# seedrum_shield_v1.net
KiCad netlist of a schematic drawn in EasyEDA
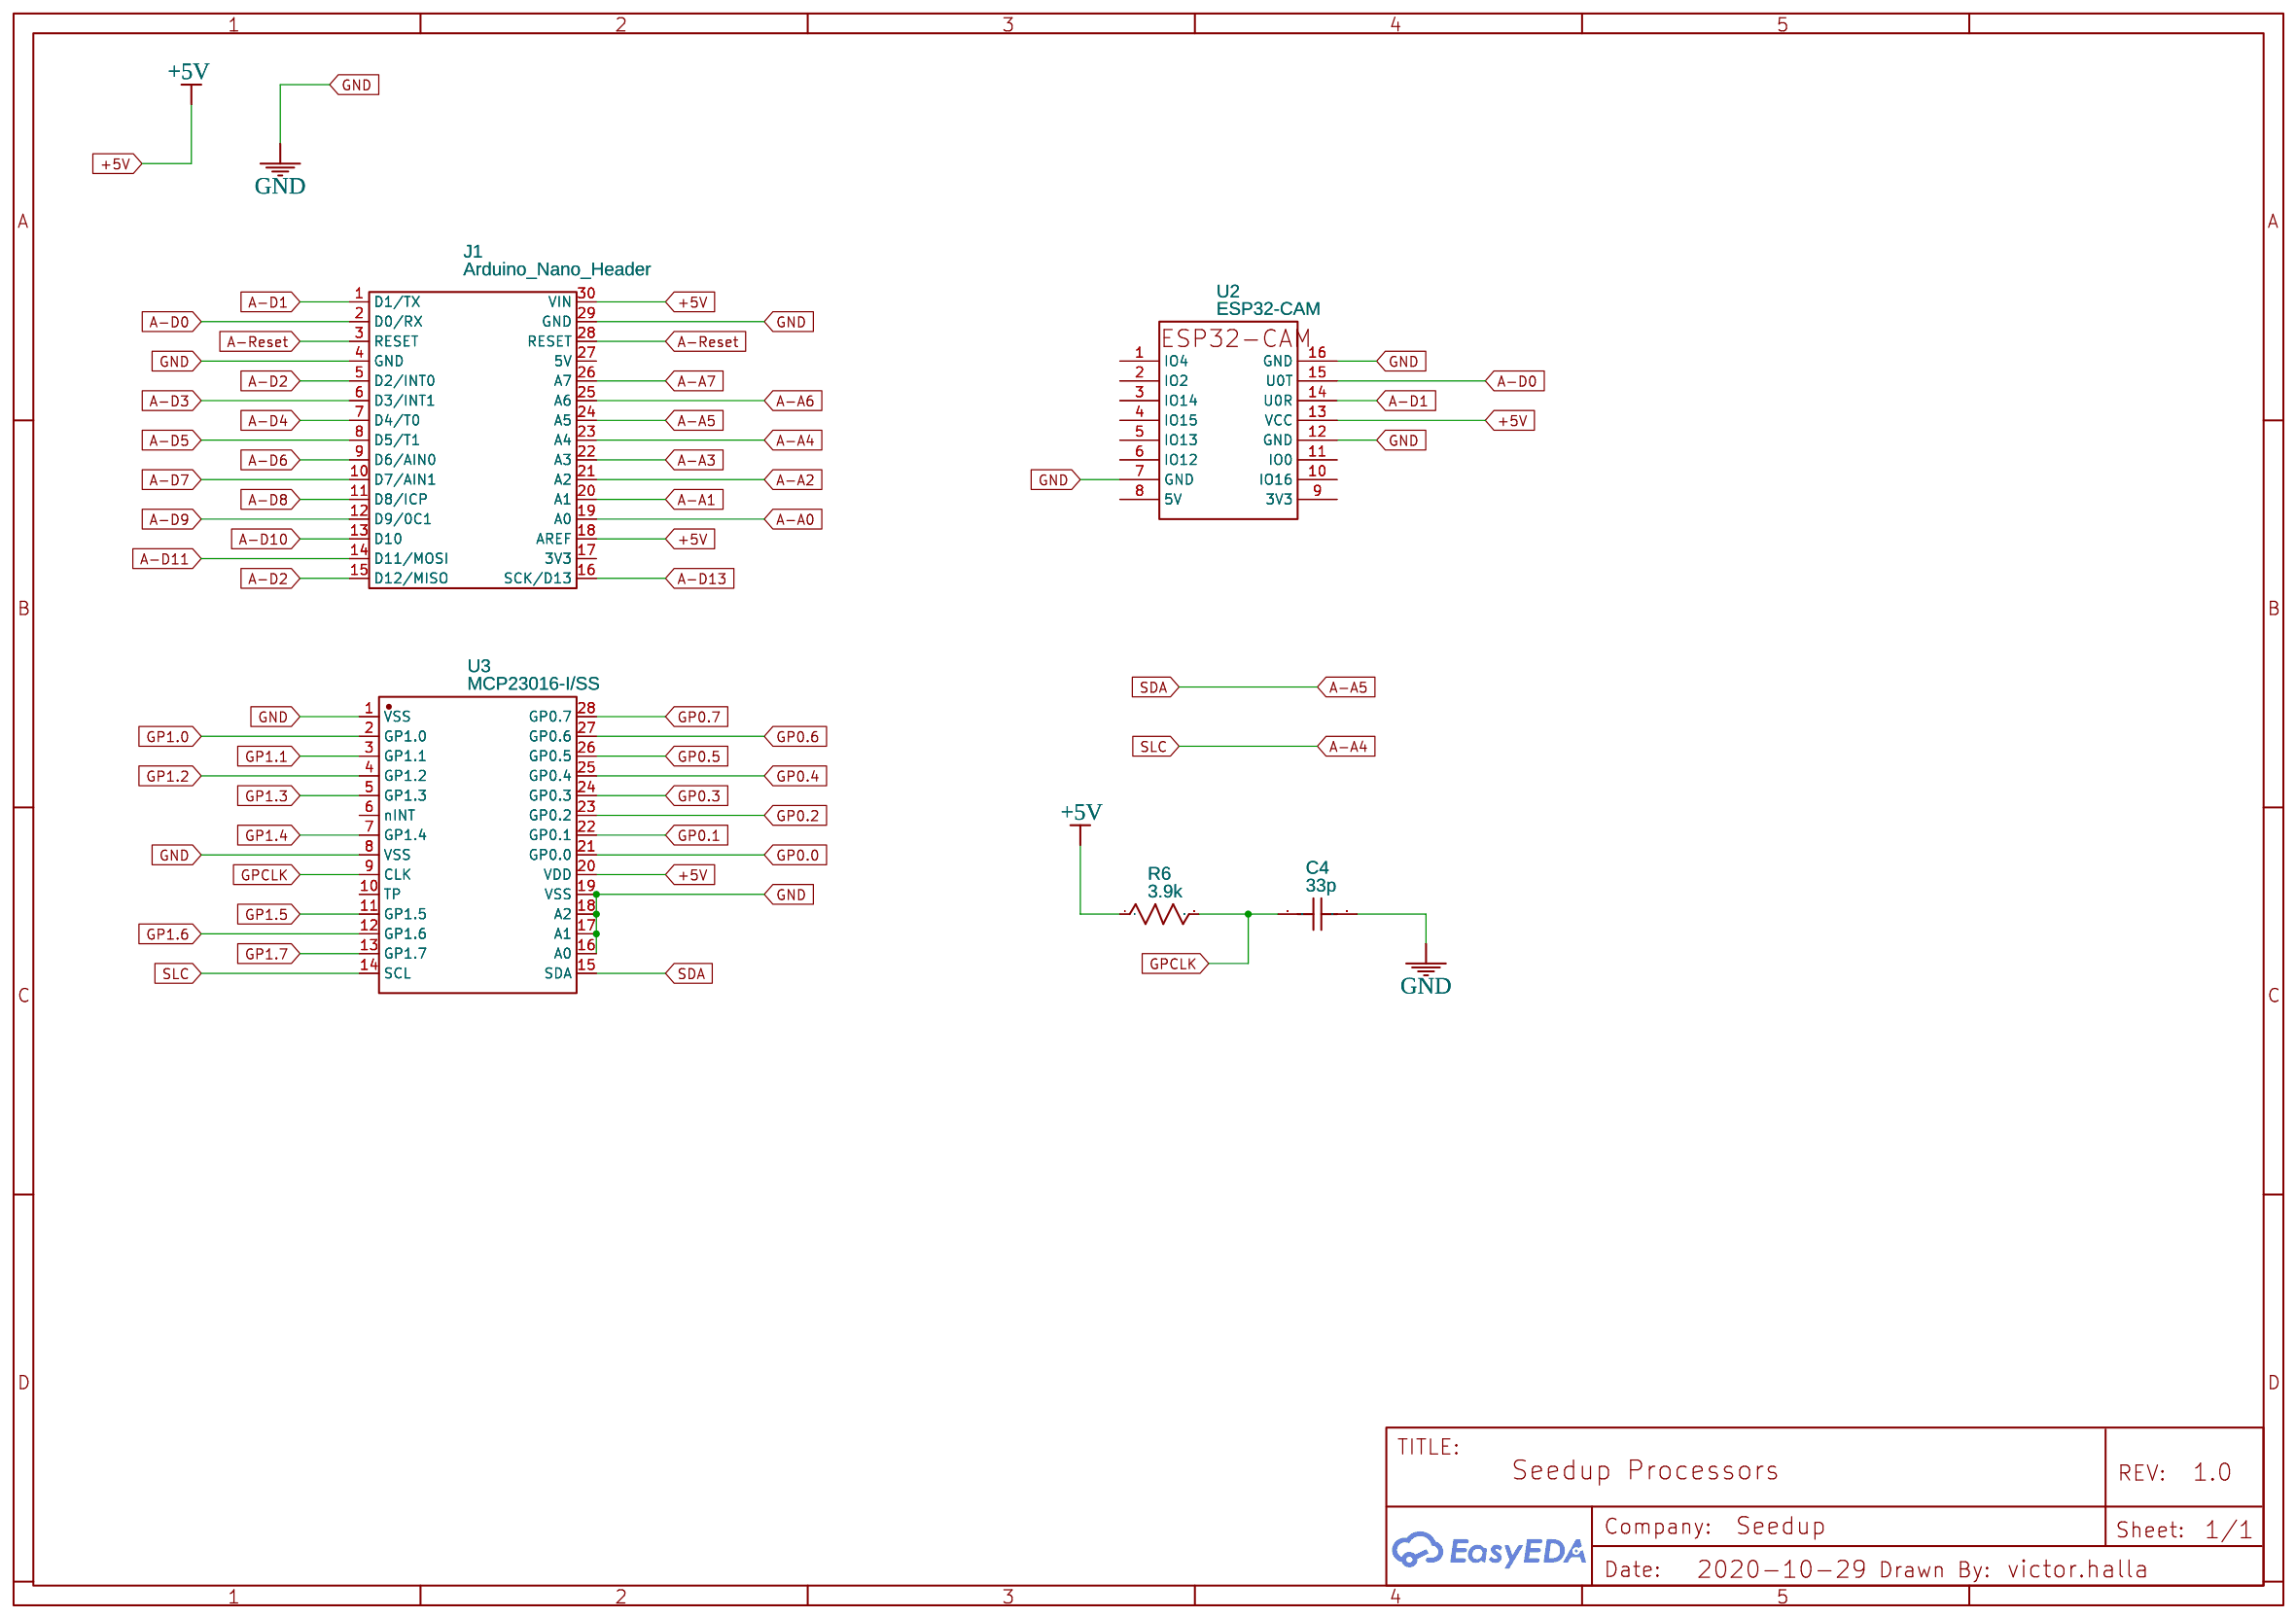
[diagram p0: Main Shield]
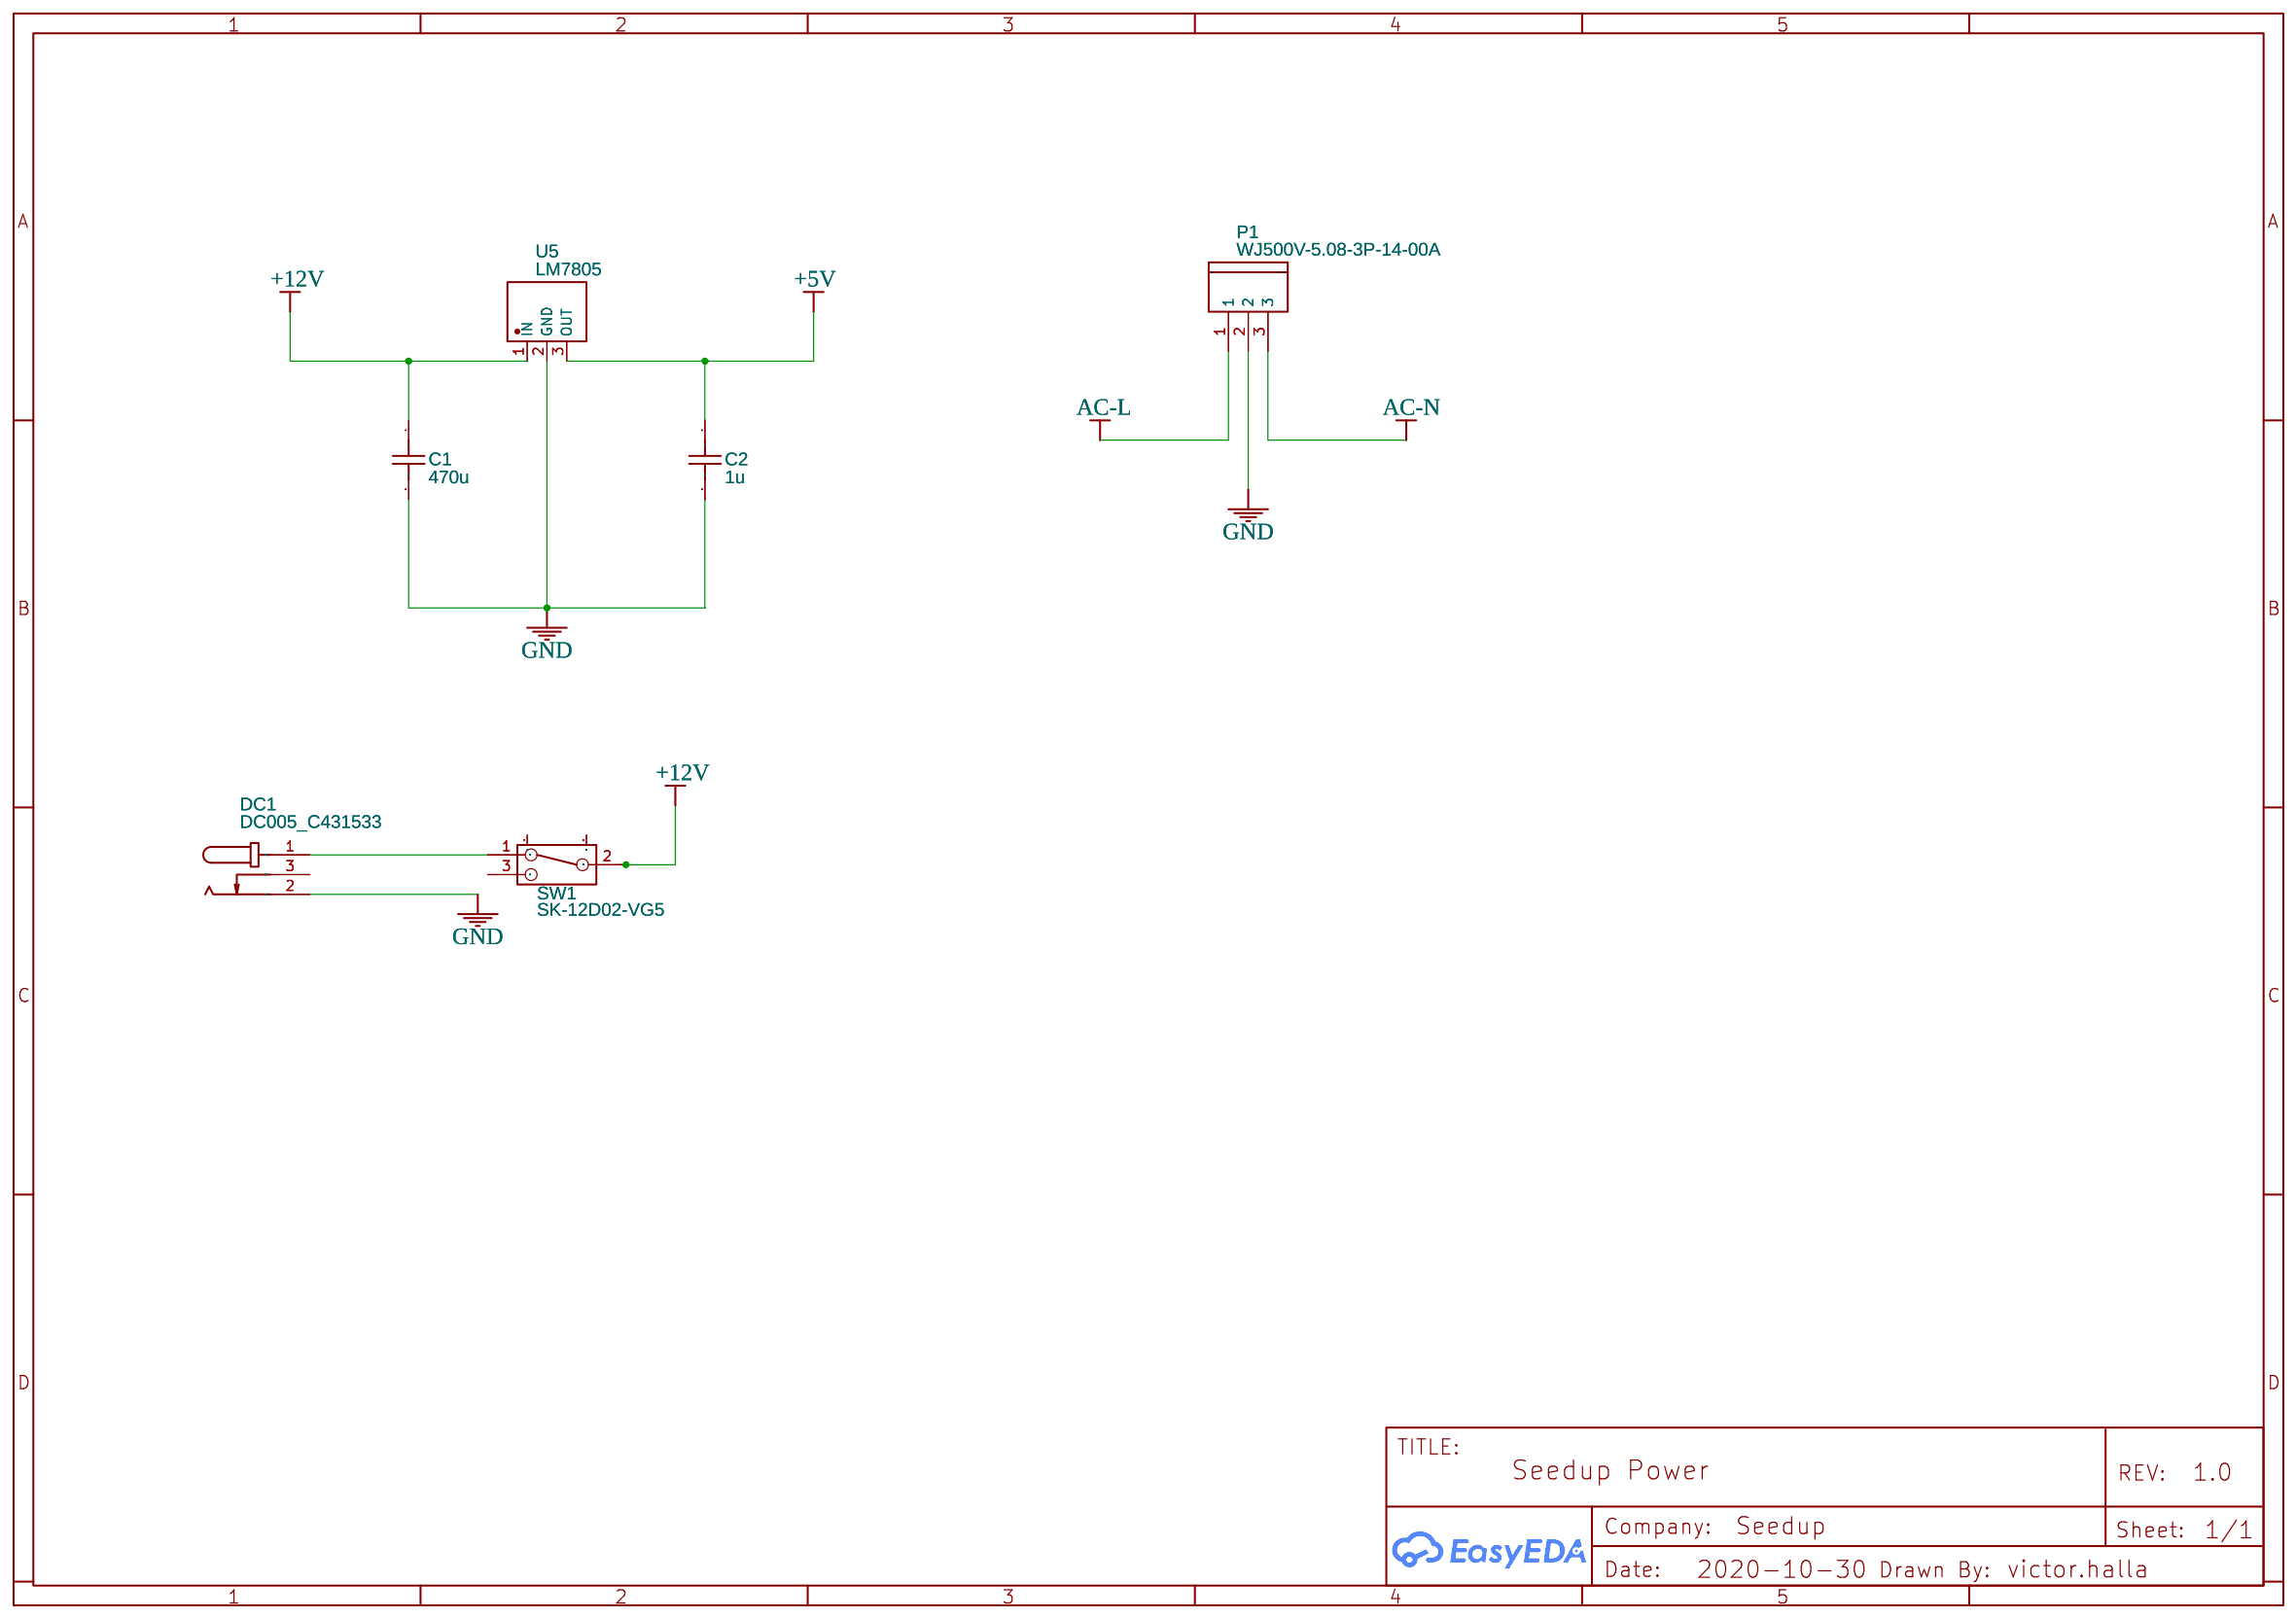
[diagram p1: Power]
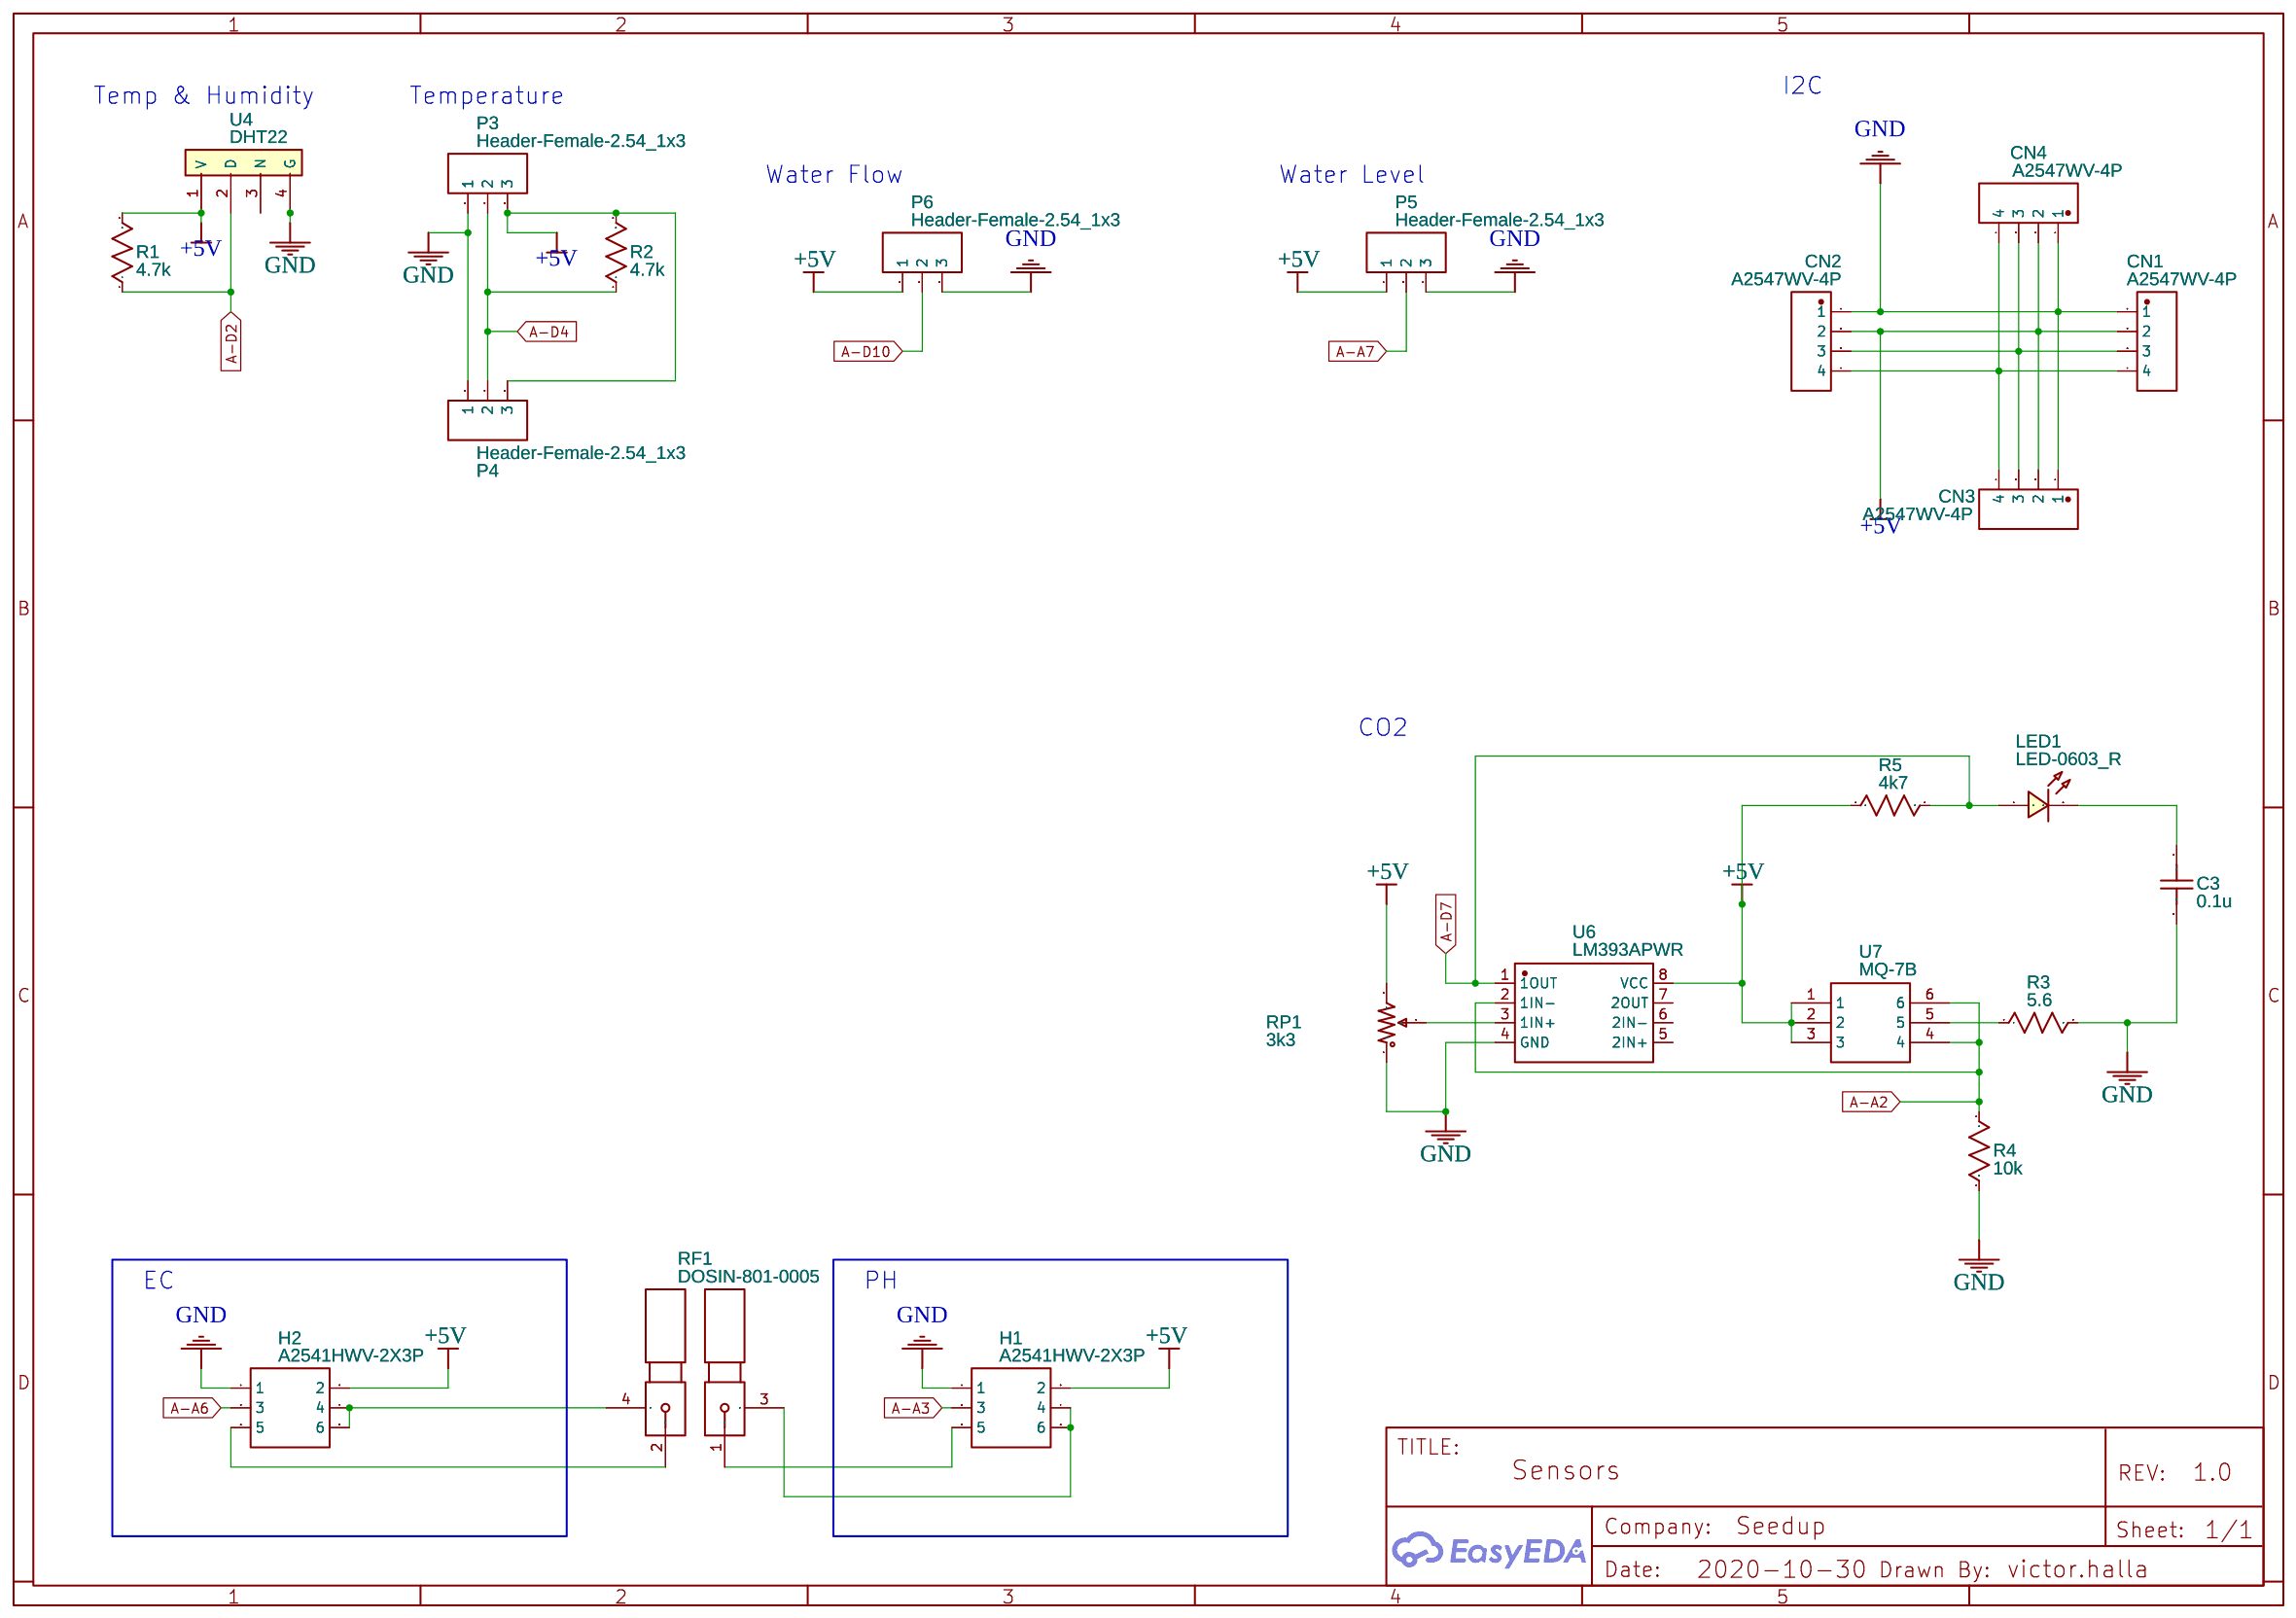
[diagram p2: Sensors]
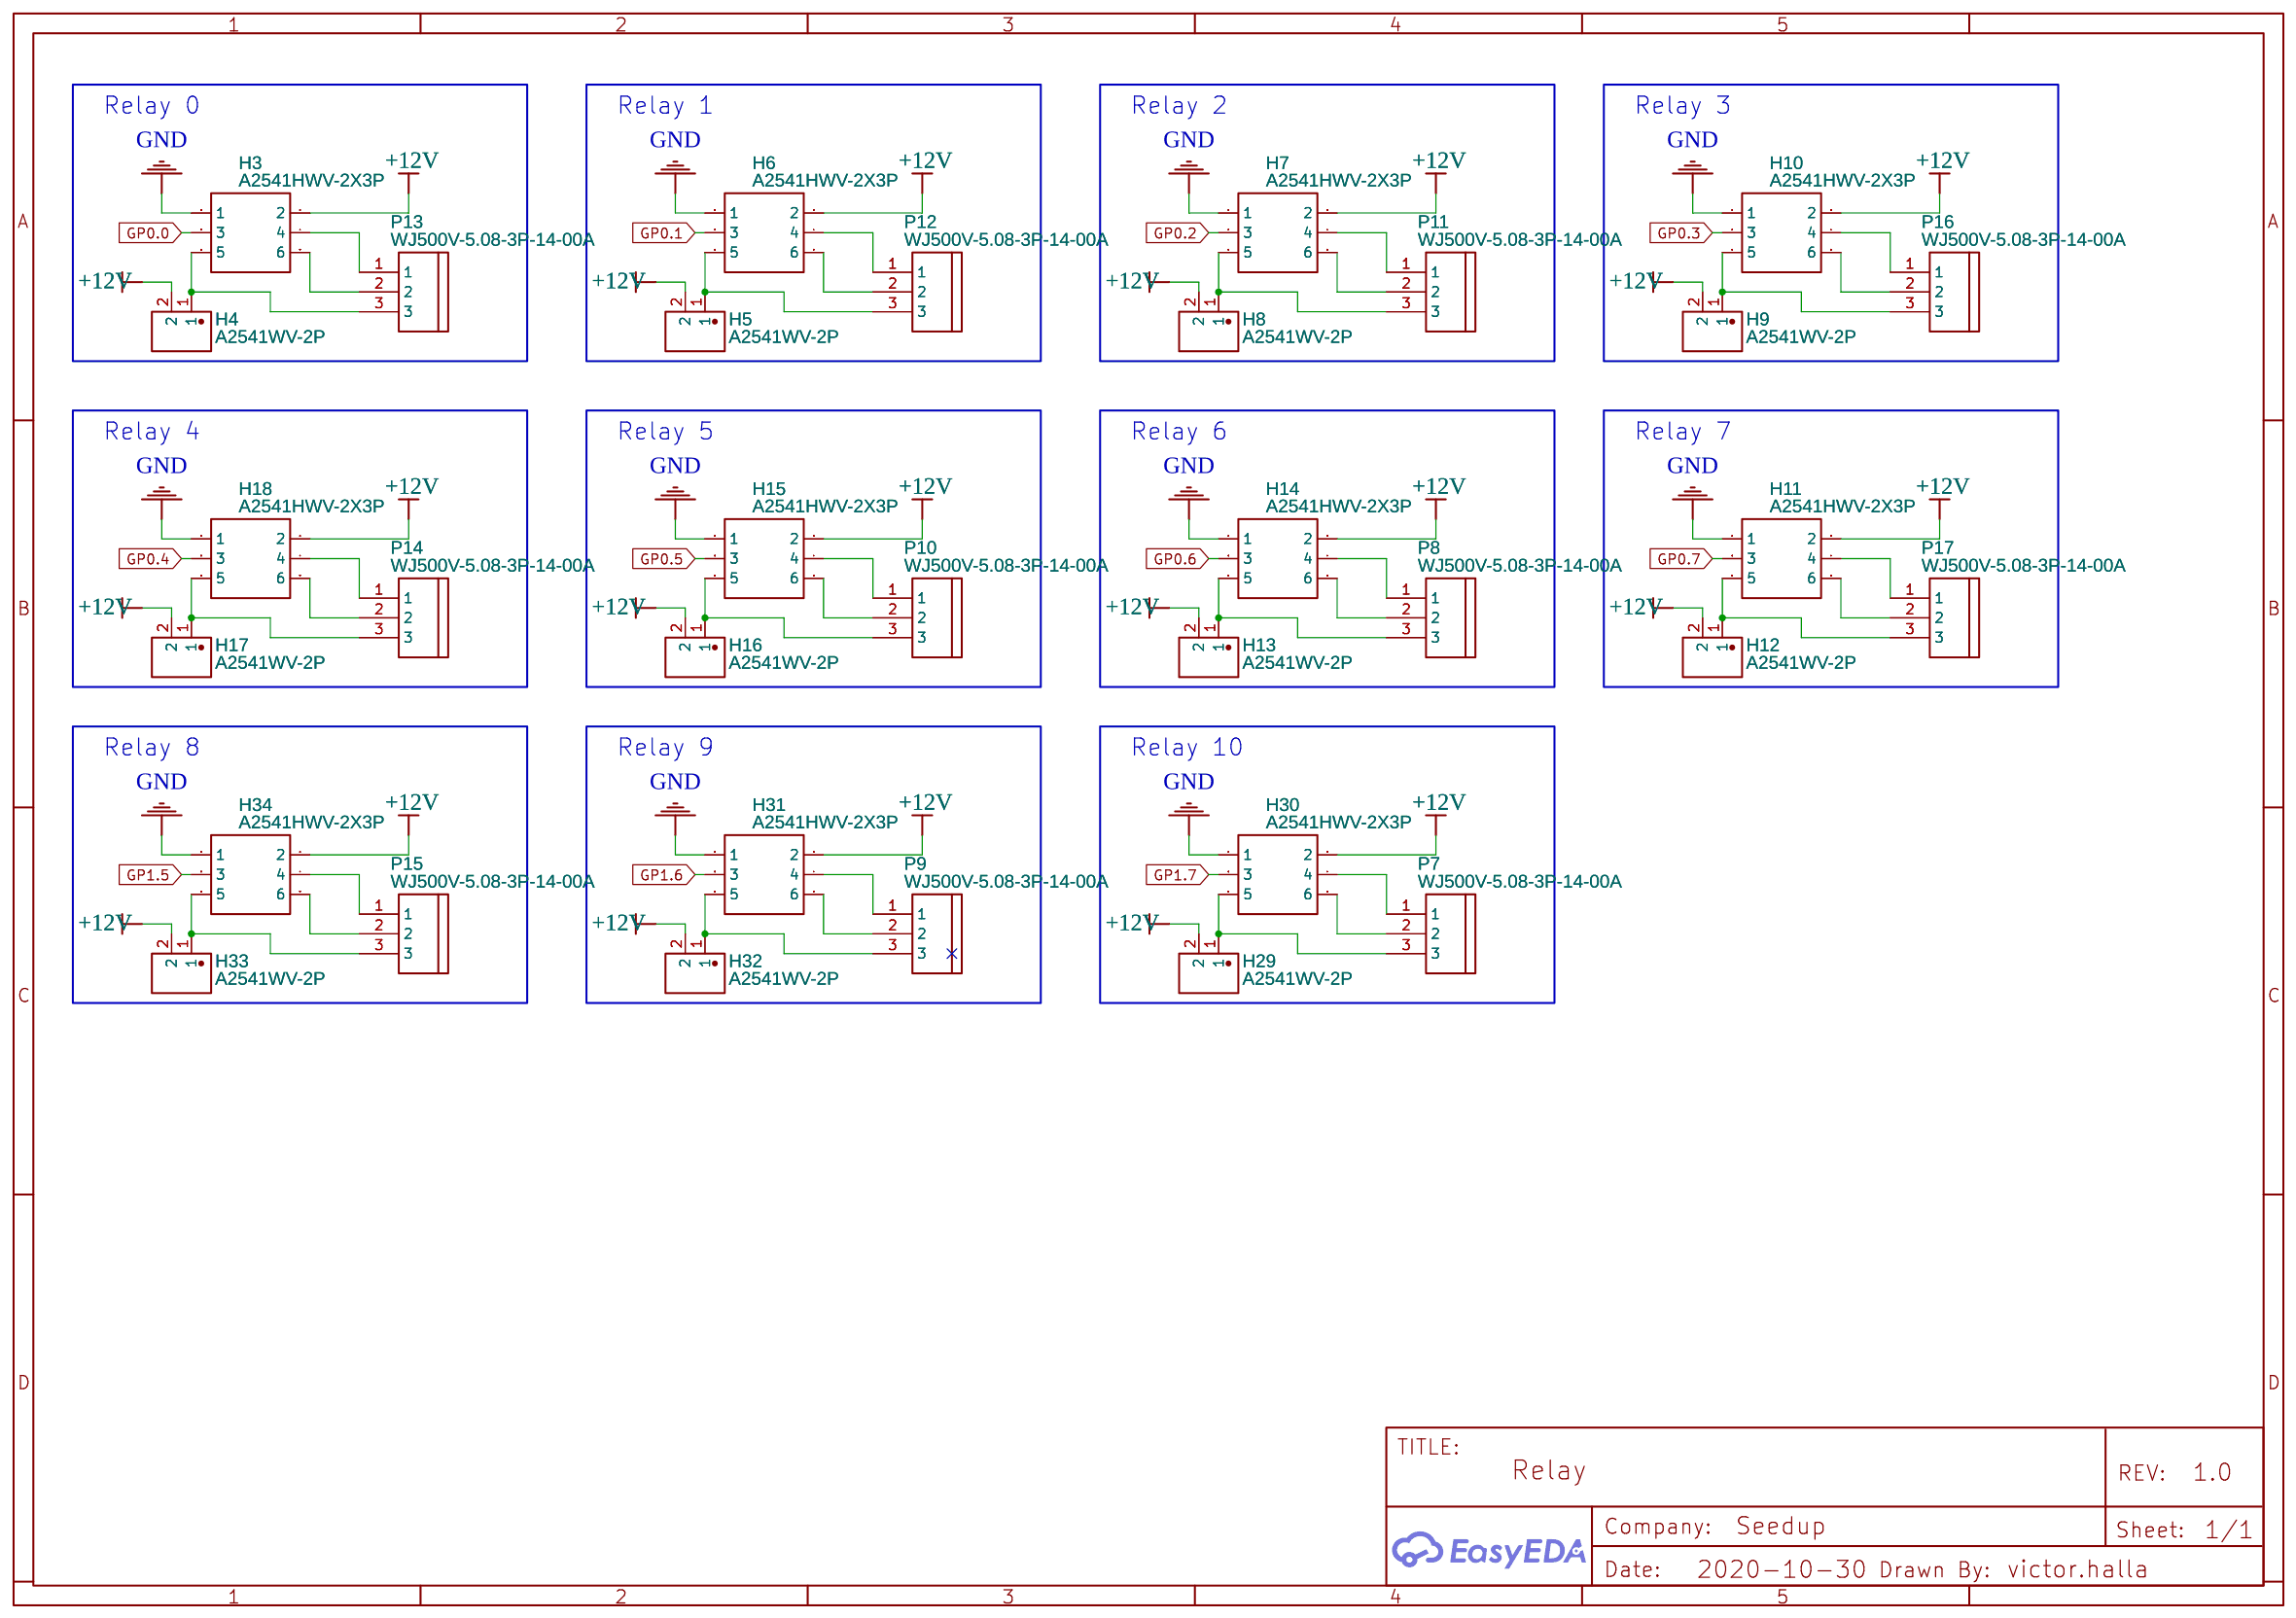
[diagram p3: Relay]
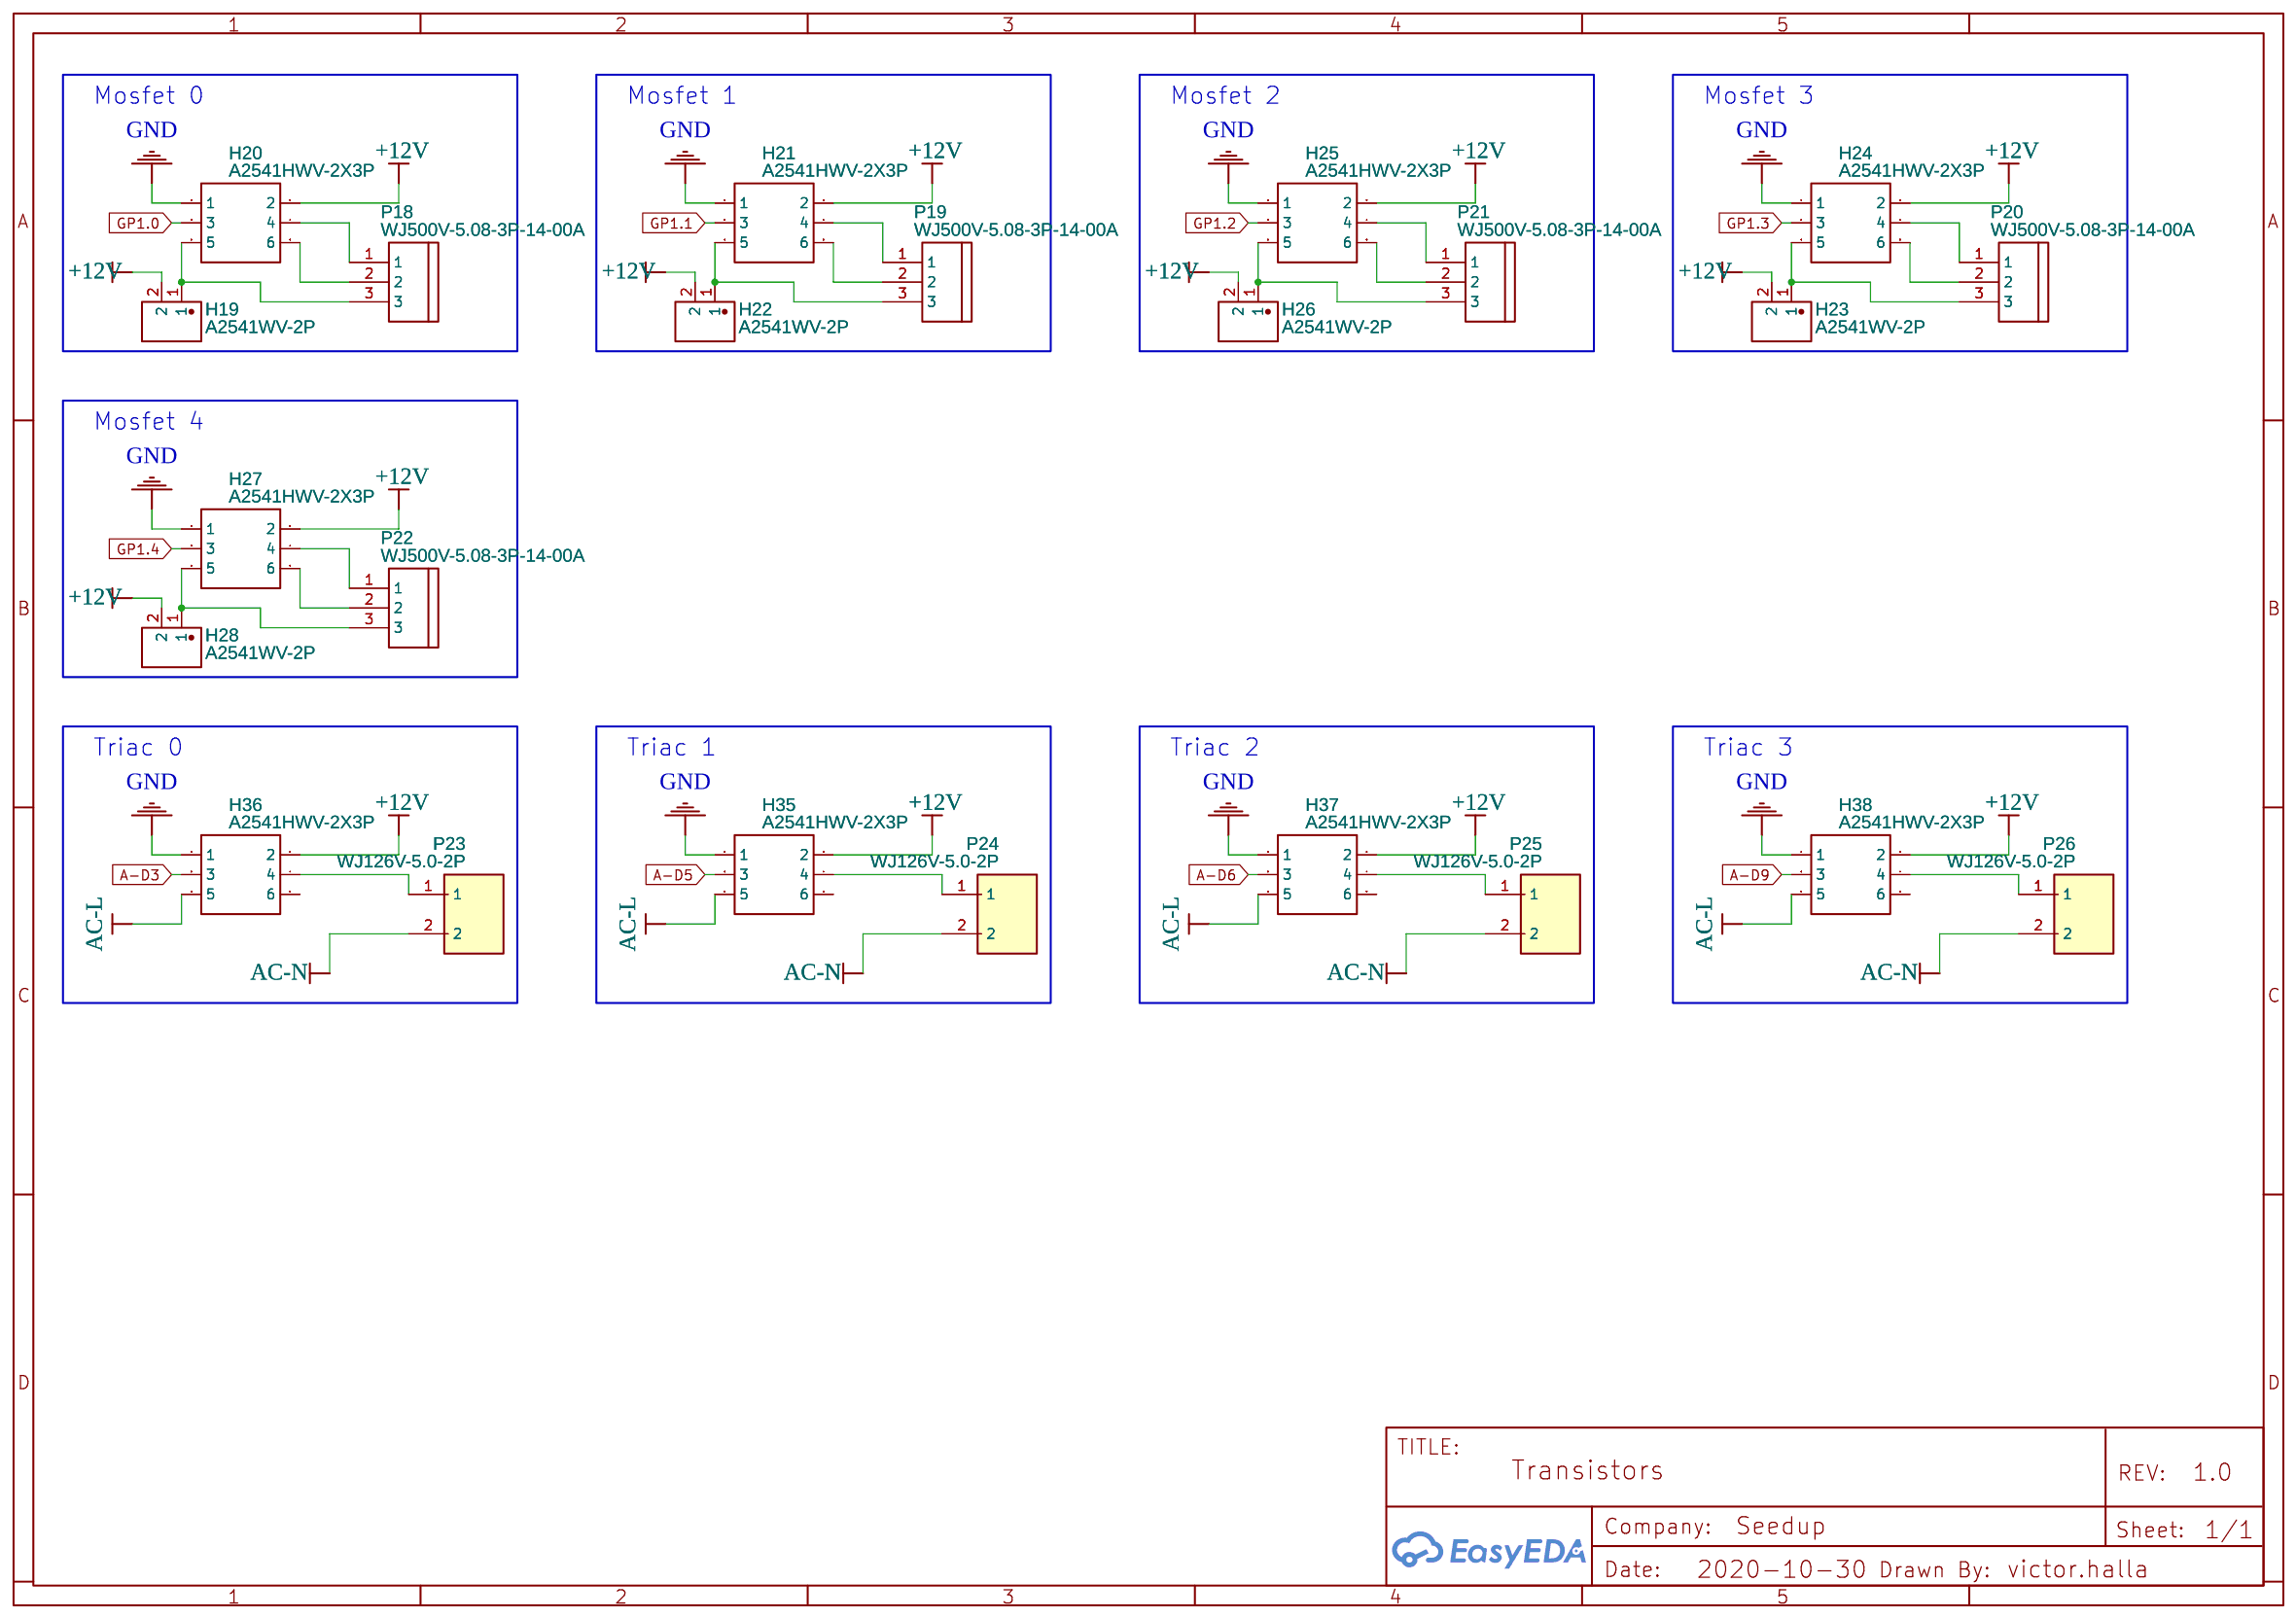
[diagram p4: Transistor]

(export (version "E")
  (design (tool "Eeschema 10.0.6"))
  (components
    (comp (ref "C4") (value "33p") (libsource (lib "") (part "C_0603_US")))
    (comp (ref "J1") (value "Arduino_Nano_Header") (libsource (lib "") (part "Arduino_Nano_Header")))
    (comp (ref "R6") (value "3.9k") (libsource (lib "") (part "R_0603_US")))
    (comp (ref "U2") (value "ESP32-CAM") (libsource (lib "") (part "ESP32-CAM")))
    (comp (ref "U3")
      (value "MCP23016-I/SS")
      (fields (field (name "BOM_Supplier Part") "C184175"))
      (libsource (lib "") (part "MCP23016-I/SS"))
    )
    (comp (ref "C1") (value "470u") (libsource (lib "") (part "C_0603_US")))
    (comp (ref "C2") (value "1u") (libsource (lib "") (part "C_0603_US")))
    (comp (ref "DC1")
      (value "DC005_C431533")
      (fields (field (name "BOM_Manufacturer Part") "DC005") (field (name "BOM_Supplier Part") "C431533"))
      (libsource (lib "") (part "DC005_C431533"))
    )
    (comp (ref "P1")
      (value "WJ500V-5.08-3P-14-00A")
      (fields (field (name "BOM_Supplier Part") "C72334"))
      (libsource (lib "") (part "WJ500V-5.08-3P-14-00A"))
    )
    (comp (ref "SW1")
      (value "SK-12D02-VG5")
      (fields (field (name "BOM_Supplier Part") "C136722"))
      (libsource (lib "") (part "SK-12D02-VG5"))
    )
    (comp (ref "U5")
      (value "LM7805")
      (fields (field (name "BOM_Supplier Part") "C845394"))
      (libsource (lib "") (part "LM7805"))
    )
    (comp (ref "C3") (value "0.1u") (libsource (lib "") (part "C_0603_US")))
    (comp (ref "CN1")
      (value "A2547WV-4P")
      (fields (field (name "BOM_Supplier Part") "C239379"))
      (libsource (lib "") (part "A2547WV-4P_1"))
    )
    (comp (ref "CN2")
      (value "A2547WV-4P")
      (fields (field (name "BOM_Supplier Part") "C239379"))
      (libsource (lib "") (part "A2547WV-4P_3"))
    )
    (comp (ref "CN3")
      (value "A2547WV-4P")
      (fields (field (name "BOM_Supplier Part") "C239379"))
      (libsource (lib "") (part "A2547WV-4P"))
    )
    (comp (ref "CN4")
      (value "A2547WV-4P")
      (fields (field (name "BOM_Supplier Part") "C239379"))
      (libsource (lib "") (part "A2547WV-4P_2"))
    )
    (comp (ref "H1")
      (value "A2541HWV-2X3P")
      (fields
        (field (name "BOM_Manufacturer Part") "A2541HWV-2x3P")
        (field (name "BOM_Supplier Part") "C239343")
      )
      (libsource (lib "") (part "A2541HWV-2X3P"))
    )
    (comp (ref "H2")
      (value "A2541HWV-2X3P")
      (fields
        (field (name "BOM_Manufacturer Part") "A2541HWV-2x3P")
        (field (name "BOM_Supplier Part") "C239343")
      )
      (libsource (lib "") (part "A2541HWV-2X3P"))
    )
    (comp (ref "LED1")
      (value "LED-0603_R")
      (fields
        (field (name "BOM_Manufacturer Part") "19-217/R6C-AL1M2VY/3T")
        (field (name "BOM_Supplier Part") "C72044")
      )
      (libsource (lib "") (part "LED-0603_R"))
    )
    (comp (ref "P3")
      (value "Header-Female-2.54_1x3")
      (fields (field (name "BOM_Supplier Part") "C146243"))
      (libsource (lib "") (part "Header-Female-2.54_1x3"))
    )
    (comp (ref "P4")
      (value "Header-Female-2.54_1x3")
      (fields (field (name "BOM_Supplier Part") "C146243"))
      (libsource (lib "") (part "Header-Female-2.54_1x3_1"))
    )
    (comp (ref "P5")
      (value "Header-Female-2.54_1x3")
      (fields (field (name "BOM_Supplier Part") "C146243"))
      (libsource (lib "") (part "Header-Female-2.54_1x3"))
    )
    (comp (ref "P6")
      (value "Header-Female-2.54_1x3")
      (fields (field (name "BOM_Supplier Part") "C146243"))
      (libsource (lib "") (part "Header-Female-2.54_1x3"))
    )
    (comp (ref "R1") (value "4.7k") (libsource (lib "") (part "R_0603_US")))
    (comp (ref "R2") (value "4.7k") (libsource (lib "") (part "R_0603_US")))
    (comp (ref "R3") (value "5.6") (libsource (lib "") (part "R_0603_US_1")))
    (comp (ref "R4") (value "10k") (libsource (lib "") (part "R_0603_US_2")))
    (comp (ref "R5") (value "4k7") (libsource (lib "") (part "R_0603_US_1")))
    (comp (ref "RF1")
      (value "DOSIN-801-0005")
      (fields (field (name "BOM_Supplier Part") "C521213"))
      (libsource (lib "") (part "DOSIN-801-0005"))
    )
    (comp (ref "RP1") (value "3k3") (libsource (lib "") (part "R_3386P_US")))
    (comp (ref "U4")
      (value "DHT22")
      (fields (field (name "BOM_Supplier Part") "PRODUCT ID: 385"))
      (libsource (lib "") (part "DHT22"))
    )
    (comp (ref "U6")
      (value "LM393APWR")
      (fields (field (name "BOM_Supplier Part") "C527473"))
      (libsource (lib "") (part "LM393APWR"))
    )
    (comp (ref "U7")
      (value "MQ-7B")
      (fields (field (name "BOM_Supplier Part") "C242495"))
      (libsource (lib "") (part "MQ-7B"))
    )
    (comp (ref "H3")
      (value "A2541HWV-2X3P")
      (fields
        (field (name "BOM_Manufacturer Part") "A2541HWV-2x3P")
        (field (name "BOM_Supplier Part") "C239343")
      )
      (libsource (lib "") (part "A2541HWV-2X3P"))
    )
    (comp (ref "H4")
      (value "A2541WV-2P")
      (fields (field (name "BOM_Supplier Part") "C225477"))
      (libsource (lib "") (part "A2541WV-2P"))
    )
    (comp (ref "H5")
      (value "A2541WV-2P")
      (fields (field (name "BOM_Supplier Part") "C225477"))
      (libsource (lib "") (part "A2541WV-2P"))
    )
    (comp (ref "H6")
      (value "A2541HWV-2X3P")
      (fields
        (field (name "BOM_Manufacturer Part") "A2541HWV-2x3P")
        (field (name "BOM_Supplier Part") "C239343")
      )
      (libsource (lib "") (part "A2541HWV-2X3P"))
    )
    (comp (ref "H7")
      (value "A2541HWV-2X3P")
      (fields
        (field (name "BOM_Manufacturer Part") "A2541HWV-2x3P")
        (field (name "BOM_Supplier Part") "C239343")
      )
      (libsource (lib "") (part "A2541HWV-2X3P"))
    )
    (comp (ref "H8")
      (value "A2541WV-2P")
      (fields (field (name "BOM_Supplier Part") "C225477"))
      (libsource (lib "") (part "A2541WV-2P"))
    )
    (comp (ref "H9")
      (value "A2541WV-2P")
      (fields (field (name "BOM_Supplier Part") "C225477"))
      (libsource (lib "") (part "A2541WV-2P"))
    )
    (comp (ref "H10")
      (value "A2541HWV-2X3P")
      (fields
        (field (name "BOM_Manufacturer Part") "A2541HWV-2x3P")
        (field (name "BOM_Supplier Part") "C239343")
      )
      (libsource (lib "") (part "A2541HWV-2X3P"))
    )
    (comp (ref "H11")
      (value "A2541HWV-2X3P")
      (fields
        (field (name "BOM_Manufacturer Part") "A2541HWV-2x3P")
        (field (name "BOM_Supplier Part") "C239343")
      )
      (libsource (lib "") (part "A2541HWV-2X3P"))
    )
    (comp (ref "H12")
      (value "A2541WV-2P")
      (fields (field (name "BOM_Supplier Part") "C225477"))
      (libsource (lib "") (part "A2541WV-2P"))
    )
    (comp (ref "H13")
      (value "A2541WV-2P")
      (fields (field (name "BOM_Supplier Part") "C225477"))
      (libsource (lib "") (part "A2541WV-2P"))
    )
    (comp (ref "H14")
      (value "A2541HWV-2X3P")
      (fields
        (field (name "BOM_Manufacturer Part") "A2541HWV-2x3P")
        (field (name "BOM_Supplier Part") "C239343")
      )
      (libsource (lib "") (part "A2541HWV-2X3P"))
    )
    (comp (ref "H15")
      (value "A2541HWV-2X3P")
      (fields
        (field (name "BOM_Manufacturer Part") "A2541HWV-2x3P")
        (field (name "BOM_Supplier Part") "C239343")
      )
      (libsource (lib "") (part "A2541HWV-2X3P"))
    )
    (comp (ref "H16")
      (value "A2541WV-2P")
      (fields (field (name "BOM_Supplier Part") "C225477"))
      (libsource (lib "") (part "A2541WV-2P"))
    )
    (comp (ref "H17")
      (value "A2541WV-2P")
      (fields (field (name "BOM_Supplier Part") "C225477"))
      (libsource (lib "") (part "A2541WV-2P"))
    )
    (comp (ref "H18")
      (value "A2541HWV-2X3P")
      (fields
        (field (name "BOM_Manufacturer Part") "A2541HWV-2x3P")
        (field (name "BOM_Supplier Part") "C239343")
      )
      (libsource (lib "") (part "A2541HWV-2X3P"))
    )
    (comp (ref "H29")
      (value "A2541WV-2P")
      (fields (field (name "BOM_Supplier Part") "C225477"))
      (libsource (lib "") (part "A2541WV-2P"))
    )
    (comp (ref "H30")
      (value "A2541HWV-2X3P")
      (fields
        (field (name "BOM_Manufacturer Part") "A2541HWV-2x3P")
        (field (name "BOM_Supplier Part") "C239343")
      )
      (libsource (lib "") (part "A2541HWV-2X3P"))
    )
    (comp (ref "H31")
      (value "A2541HWV-2X3P")
      (fields
        (field (name "BOM_Manufacturer Part") "A2541HWV-2x3P")
        (field (name "BOM_Supplier Part") "C239343")
      )
      (libsource (lib "") (part "A2541HWV-2X3P"))
    )
    (comp (ref "H32")
      (value "A2541WV-2P")
      (fields (field (name "BOM_Supplier Part") "C225477"))
      (libsource (lib "") (part "A2541WV-2P"))
    )
    (comp (ref "H33")
      (value "A2541WV-2P")
      (fields (field (name "BOM_Supplier Part") "C225477"))
      (libsource (lib "") (part "A2541WV-2P"))
    )
    (comp (ref "H34")
      (value "A2541HWV-2X3P")
      (fields
        (field (name "BOM_Manufacturer Part") "A2541HWV-2x3P")
        (field (name "BOM_Supplier Part") "C239343")
      )
      (libsource (lib "") (part "A2541HWV-2X3P"))
    )
    (comp (ref "P7")
      (value "WJ500V-5.08-3P-14-00A")
      (fields (field (name "BOM_Supplier Part") "C72334"))
      (libsource (lib "") (part "WJ500V-5.08-3P-14-00A"))
    )
    (comp (ref "P8")
      (value "WJ500V-5.08-3P-14-00A")
      (fields (field (name "BOM_Supplier Part") "C72334"))
      (libsource (lib "") (part "WJ500V-5.08-3P-14-00A"))
    )
    (comp (ref "P9")
      (value "WJ500V-5.08-3P-14-00A")
      (fields (field (name "BOM_Supplier Part") "C72334"))
      (libsource (lib "") (part "WJ500V-5.08-3P-14-00A"))
    )
    (comp (ref "P10")
      (value "WJ500V-5.08-3P-14-00A")
      (fields (field (name "BOM_Supplier Part") "C72334"))
      (libsource (lib "") (part "WJ500V-5.08-3P-14-00A"))
    )
    (comp (ref "P11")
      (value "WJ500V-5.08-3P-14-00A")
      (fields (field (name "BOM_Supplier Part") "C72334"))
      (libsource (lib "") (part "WJ500V-5.08-3P-14-00A"))
    )
    (comp (ref "P12")
      (value "WJ500V-5.08-3P-14-00A")
      (fields (field (name "BOM_Supplier Part") "C72334"))
      (libsource (lib "") (part "WJ500V-5.08-3P-14-00A"))
    )
    (comp (ref "P13")
      (value "WJ500V-5.08-3P-14-00A")
      (fields (field (name "BOM_Supplier Part") "C72334"))
      (libsource (lib "") (part "WJ500V-5.08-3P-14-00A"))
    )
    (comp (ref "P14")
      (value "WJ500V-5.08-3P-14-00A")
      (fields (field (name "BOM_Supplier Part") "C72334"))
      (libsource (lib "") (part "WJ500V-5.08-3P-14-00A"))
    )
    (comp (ref "P15")
      (value "WJ500V-5.08-3P-14-00A")
      (fields (field (name "BOM_Supplier Part") "C72334"))
      (libsource (lib "") (part "WJ500V-5.08-3P-14-00A"))
    )
    (comp (ref "P16")
      (value "WJ500V-5.08-3P-14-00A")
      (fields (field (name "BOM_Supplier Part") "C72334"))
      (libsource (lib "") (part "WJ500V-5.08-3P-14-00A"))
    )
    (comp (ref "P17")
      (value "WJ500V-5.08-3P-14-00A")
      (fields (field (name "BOM_Supplier Part") "C72334"))
      (libsource (lib "") (part "WJ500V-5.08-3P-14-00A"))
    )
    (comp (ref "H19")
      (value "A2541WV-2P")
      (fields (field (name "BOM_Supplier Part") "C225477"))
      (libsource (lib "") (part "A2541WV-2P"))
    )
    (comp (ref "H20")
      (value "A2541HWV-2X3P")
      (fields
        (field (name "BOM_Manufacturer Part") "A2541HWV-2x3P")
        (field (name "BOM_Supplier Part") "C239343")
      )
      (libsource (lib "") (part "A2541HWV-2X3P"))
    )
    (comp (ref "H21")
      (value "A2541HWV-2X3P")
      (fields
        (field (name "BOM_Manufacturer Part") "A2541HWV-2x3P")
        (field (name "BOM_Supplier Part") "C239343")
      )
      (libsource (lib "") (part "A2541HWV-2X3P"))
    )
    (comp (ref "H22")
      (value "A2541WV-2P")
      (fields (field (name "BOM_Supplier Part") "C225477"))
      (libsource (lib "") (part "A2541WV-2P"))
    )
    (comp (ref "H23")
      (value "A2541WV-2P")
      (fields (field (name "BOM_Supplier Part") "C225477"))
      (libsource (lib "") (part "A2541WV-2P"))
    )
    (comp (ref "H24")
      (value "A2541HWV-2X3P")
      (fields
        (field (name "BOM_Manufacturer Part") "A2541HWV-2x3P")
        (field (name "BOM_Supplier Part") "C239343")
      )
      (libsource (lib "") (part "A2541HWV-2X3P"))
    )
    (comp (ref "H25")
      (value "A2541HWV-2X3P")
      (fields
        (field (name "BOM_Manufacturer Part") "A2541HWV-2x3P")
        (field (name "BOM_Supplier Part") "C239343")
      )
      (libsource (lib "") (part "A2541HWV-2X3P"))
    )
    (comp (ref "H26")
      (value "A2541WV-2P")
      (fields (field (name "BOM_Supplier Part") "C225477"))
      (libsource (lib "") (part "A2541WV-2P"))
    )
    (comp (ref "H27")
      (value "A2541HWV-2X3P")
      (fields
        (field (name "BOM_Manufacturer Part") "A2541HWV-2x3P")
        (field (name "BOM_Supplier Part") "C239343")
      )
      (libsource (lib "") (part "A2541HWV-2X3P"))
    )
    (comp (ref "H28")
      (value "A2541WV-2P")
      (fields (field (name "BOM_Supplier Part") "C225477"))
      (libsource (lib "") (part "A2541WV-2P"))
    )
    (comp (ref "H35")
      (value "A2541HWV-2X3P")
      (fields
        (field (name "BOM_Manufacturer Part") "A2541HWV-2x3P")
        (field (name "BOM_Supplier Part") "C239343")
      )
      (libsource (lib "") (part "A2541HWV-2X3P"))
    )
    (comp (ref "H36")
      (value "A2541HWV-2X3P")
      (fields
        (field (name "BOM_Manufacturer Part") "A2541HWV-2x3P")
        (field (name "BOM_Supplier Part") "C239343")
      )
      (libsource (lib "") (part "A2541HWV-2X3P"))
    )
    (comp (ref "H37")
      (value "A2541HWV-2X3P")
      (fields
        (field (name "BOM_Manufacturer Part") "A2541HWV-2x3P")
        (field (name "BOM_Supplier Part") "C239343")
      )
      (libsource (lib "") (part "A2541HWV-2X3P"))
    )
    (comp (ref "H38")
      (value "A2541HWV-2X3P")
      (fields
        (field (name "BOM_Manufacturer Part") "A2541HWV-2x3P")
        (field (name "BOM_Supplier Part") "C239343")
      )
      (libsource (lib "") (part "A2541HWV-2X3P"))
    )
    (comp (ref "P18")
      (value "WJ500V-5.08-3P-14-00A")
      (fields (field (name "BOM_Supplier Part") "C72334"))
      (libsource (lib "") (part "WJ500V-5.08-3P-14-00A"))
    )
    (comp (ref "P19")
      (value "WJ500V-5.08-3P-14-00A")
      (fields (field (name "BOM_Supplier Part") "C72334"))
      (libsource (lib "") (part "WJ500V-5.08-3P-14-00A"))
    )
    (comp (ref "P20")
      (value "WJ500V-5.08-3P-14-00A")
      (fields (field (name "BOM_Supplier Part") "C72334"))
      (libsource (lib "") (part "WJ500V-5.08-3P-14-00A"))
    )
    (comp (ref "P21")
      (value "WJ500V-5.08-3P-14-00A")
      (fields (field (name "BOM_Supplier Part") "C72334"))
      (libsource (lib "") (part "WJ500V-5.08-3P-14-00A"))
    )
    (comp (ref "P22")
      (value "WJ500V-5.08-3P-14-00A")
      (fields (field (name "BOM_Supplier Part") "C72334"))
      (libsource (lib "") (part "WJ500V-5.08-3P-14-00A"))
    )
    (comp (ref "P23")
      (value "WJ126V-5.0-2P")
      (fields (field (name "BOM_Supplier Part") "C8404"))
      (libsource (lib "") (part "WJ126V-5.0-2P"))
    )
    (comp (ref "P24")
      (value "WJ126V-5.0-2P")
      (fields (field (name "BOM_Supplier Part") "C8404"))
      (libsource (lib "") (part "WJ126V-5.0-2P"))
    )
    (comp (ref "P25")
      (value "WJ126V-5.0-2P")
      (fields (field (name "BOM_Supplier Part") "C8404"))
      (libsource (lib "") (part "WJ126V-5.0-2P"))
    )
    (comp (ref "P26")
      (value "WJ126V-5.0-2P")
      (fields (field (name "BOM_Supplier Part") "C8404"))
      (libsource (lib "") (part "WJ126V-5.0-2P"))
    )
  )
  (nets
    (net (code "1") (name "+5V") (class "Default")
      (node (ref "C2") (pin "1") (pinfunction "1_1") (pintype "unspecified"))
      (node (ref "CN1") (pin "2") (pinfunction "2_2") (pintype "unspecified"))
      (node (ref "CN2") (pin "2") (pinfunction "2_2") (pintype "unspecified"))
      (node (ref "CN3") (pin "2") (pinfunction "2_2") (pintype "unspecified"))
      (node (ref "CN4") (pin "2") (pinfunction "2_2") (pintype "unspecified"))
      (node (ref "H1") (pin "2") (pinfunction "2_2") (pintype "input"))
      (node (ref "H2") (pin "2") (pinfunction "2_2") (pintype "input"))
      (node (ref "J1") (pin "18") (pinfunction "AREF_18") (pintype "unspecified"))
      (node (ref "J1") (pin "30") (pinfunction "VIN_30") (pintype "unspecified"))
      (node (ref "P3") (pin "3") (pinfunction "3_3") (pintype "input"))
      (node (ref "P4") (pin "3") (pinfunction "3_3") (pintype "input"))
      (node (ref "P5") (pin "1") (pinfunction "1_1") (pintype "input"))
      (node (ref "P6") (pin "1") (pinfunction "1_1") (pintype "input"))
      (node (ref "R1") (pin "2") (pinfunction "2_2") (pintype "unspecified"))
      (node (ref "R2") (pin "2") (pinfunction "2_2") (pintype "unspecified"))
      (node (ref "R5") (pin "1") (pinfunction "1_1") (pintype "unspecified"))
      (node (ref "R6") (pin "1") (pinfunction "1_1") (pintype "unspecified"))
      (node (ref "RP1") (pin "3") (pinfunction "3_3") (pintype "unspecified"))
      (node (ref "U2") (pin "13") (pinfunction "VCC_13") (pintype "unspecified"))
      (node (ref "U3") (pin "20") (pinfunction "VDD_20") (pintype "unspecified"))
      (node (ref "U4") (pin "1") (pinfunction "V_1") (pintype "unspecified"))
      (node (ref "U5") (pin "3") (pinfunction "OUT_3") (pintype "unspecified"))
      (node (ref "U6") (pin "8") (pinfunction "VCC_8") (pintype "unspecified"))
      (node (ref "U7") (pin "1") (pinfunction "1_1") (pintype "unspecified"))
      (node (ref "U7") (pin "2") (pinfunction "2_2") (pintype "unspecified"))
      (node (ref "U7") (pin "3") (pinfunction "3_3") (pintype "unspecified"))
    )
    (net (code "2") (name "+12V") (class "Default")
      (node (ref "C1") (pin "1") (pinfunction "1_1") (pintype "unspecified"))
      (node (ref "H10") (pin "2") (pinfunction "2_2") (pintype "input"))
      (node (ref "H11") (pin "2") (pinfunction "2_2") (pintype "input"))
      (node (ref "H12") (pin "2") (pinfunction "2_2") (pintype "unspecified"))
      (node (ref "H13") (pin "2") (pinfunction "2_2") (pintype "unspecified"))
      (node (ref "H14") (pin "2") (pinfunction "2_2") (pintype "input"))
      (node (ref "H15") (pin "2") (pinfunction "2_2") (pintype "input"))
      (node (ref "H16") (pin "2") (pinfunction "2_2") (pintype "unspecified"))
      (node (ref "H17") (pin "2") (pinfunction "2_2") (pintype "unspecified"))
      (node (ref "H18") (pin "2") (pinfunction "2_2") (pintype "input"))
      (node (ref "H19") (pin "2") (pinfunction "2_2") (pintype "unspecified"))
      (node (ref "H20") (pin "2") (pinfunction "2_2") (pintype "input"))
      (node (ref "H21") (pin "2") (pinfunction "2_2") (pintype "input"))
      (node (ref "H22") (pin "2") (pinfunction "2_2") (pintype "unspecified"))
      (node (ref "H23") (pin "2") (pinfunction "2_2") (pintype "unspecified"))
      (node (ref "H24") (pin "2") (pinfunction "2_2") (pintype "input"))
      (node (ref "H25") (pin "2") (pinfunction "2_2") (pintype "input"))
      (node (ref "H26") (pin "2") (pinfunction "2_2") (pintype "unspecified"))
      (node (ref "H27") (pin "2") (pinfunction "2_2") (pintype "input"))
      (node (ref "H28") (pin "2") (pinfunction "2_2") (pintype "unspecified"))
      (node (ref "H29") (pin "2") (pinfunction "2_2") (pintype "unspecified"))
      (node (ref "H3") (pin "2") (pinfunction "2_2") (pintype "input"))
      (node (ref "H30") (pin "2") (pinfunction "2_2") (pintype "input"))
      (node (ref "H31") (pin "2") (pinfunction "2_2") (pintype "input"))
      (node (ref "H32") (pin "2") (pinfunction "2_2") (pintype "unspecified"))
      (node (ref "H33") (pin "2") (pinfunction "2_2") (pintype "unspecified"))
      (node (ref "H34") (pin "2") (pinfunction "2_2") (pintype "input"))
      (node (ref "H35") (pin "2") (pinfunction "2_2") (pintype "input"))
      (node (ref "H36") (pin "2") (pinfunction "2_2") (pintype "input"))
      (node (ref "H37") (pin "2") (pinfunction "2_2") (pintype "input"))
      (node (ref "H38") (pin "2") (pinfunction "2_2") (pintype "input"))
      (node (ref "H4") (pin "2") (pinfunction "2_2") (pintype "unspecified"))
      (node (ref "H5") (pin "2") (pinfunction "2_2") (pintype "unspecified"))
      (node (ref "H6") (pin "2") (pinfunction "2_2") (pintype "input"))
      (node (ref "H7") (pin "2") (pinfunction "2_2") (pintype "input"))
      (node (ref "H8") (pin "2") (pinfunction "2_2") (pintype "unspecified"))
      (node (ref "H9") (pin "2") (pinfunction "2_2") (pintype "unspecified"))
      (node (ref "SW1") (pin "2") (pinfunction "2_2") (pintype "unspecified"))
      (node (ref "U5") (pin "1") (pinfunction "IN_1") (pintype "unspecified"))
    )
    (net (code "3") (name "A-A0") (class "Default")
      (node (ref "J1") (pin "19") (pinfunction "A0_19") (pintype "unspecified"))
    )
    (net (code "4") (name "A-A1") (class "Default")
      (node (ref "J1") (pin "20") (pinfunction "A1_20") (pintype "unspecified"))
    )
    (net (code "5") (name "A-A2") (class "Default")
      (node (ref "J1") (pin "21") (pinfunction "A2_21") (pintype "unspecified"))
      (node (ref "R4") (pin "1") (pinfunction "1_1") (pintype "unspecified"))
      (node (ref "U6") (pin "2") (pinfunction "1IN−_2") (pintype "unspecified"))
      (node (ref "U7") (pin "4") (pinfunction "4_4") (pintype "unspecified"))
      (node (ref "U7") (pin "6") (pinfunction "6_6") (pintype "unspecified"))
    )
    (net (code "6") (name "A-A3") (class "Default")
      (node (ref "H1") (pin "3") (pinfunction "3_3") (pintype "input"))
      (node (ref "J1") (pin "22") (pinfunction "A3_22") (pintype "unspecified"))
    )
    (net (code "7") (name "A-A4") (class "Default")
      (node (ref "J1") (pin "23") (pinfunction "A4_23") (pintype "unspecified"))
      (node (ref "U3") (pin "14") (pinfunction "SCL_14") (pintype "unspecified"))
    )
    (net (code "8") (name "A-A5") (class "Default")
      (node (ref "J1") (pin "24") (pinfunction "A5_24") (pintype "unspecified"))
      (node (ref "U3") (pin "15") (pinfunction "SDA_15") (pintype "unspecified"))
    )
    (net (code "9") (name "A-A6") (class "Default")
      (node (ref "H2") (pin "3") (pinfunction "3_3") (pintype "input"))
      (node (ref "J1") (pin "25") (pinfunction "A6_25") (pintype "unspecified"))
    )
    (net (code "10") (name "A-A7") (class "Default")
      (node (ref "J1") (pin "26") (pinfunction "A7_26") (pintype "unspecified"))
      (node (ref "P5") (pin "2") (pinfunction "2_2") (pintype "input"))
    )
    (net (code "11") (name "A-D0") (class "Default")
      (node (ref "J1") (pin "2") (pinfunction "D0/RX_2") (pintype "unspecified"))
      (node (ref "U2") (pin "15") (pinfunction "U0T_15") (pintype "unspecified"))
    )
    (net (code "12") (name "A-D1") (class "Default")
      (node (ref "J1") (pin "1") (pinfunction "D1/TX_1") (pintype "unspecified"))
      (node (ref "U2") (pin "14") (pinfunction "U0R_14") (pintype "unspecified"))
    )
    (net (code "13") (name "A-D2") (class "Default")
      (node (ref "J1") (pin "15") (pinfunction "D12/MISO_15") (pintype "unspecified"))
      (node (ref "J1") (pin "5") (pinfunction "D2/INT0_5") (pintype "unspecified"))
      (node (ref "R1") (pin "1") (pinfunction "1_1") (pintype "unspecified"))
      (node (ref "U4") (pin "2") (pinfunction "D_2") (pintype "unspecified"))
    )
    (net (code "14") (name "A-D3") (class "Default")
      (node (ref "H36") (pin "3") (pinfunction "3_3") (pintype "input"))
      (node (ref "J1") (pin "6") (pinfunction "D3/INT1_6") (pintype "unspecified"))
    )
    (net (code "15") (name "A-D4") (class "Default")
      (node (ref "J1") (pin "7") (pinfunction "D4/T0_7") (pintype "unspecified"))
      (node (ref "P3") (pin "2") (pinfunction "2_2") (pintype "input"))
      (node (ref "P4") (pin "2") (pinfunction "2_2") (pintype "input"))
      (node (ref "R2") (pin "1") (pinfunction "1_1") (pintype "unspecified"))
    )
    (net (code "16") (name "A-D5") (class "Default")
      (node (ref "H35") (pin "3") (pinfunction "3_3") (pintype "input"))
      (node (ref "J1") (pin "8") (pinfunction "D5/T1_8") (pintype "unspecified"))
    )
    (net (code "17") (name "A-D6") (class "Default")
      (node (ref "H37") (pin "3") (pinfunction "3_3") (pintype "input"))
      (node (ref "J1") (pin "9") (pinfunction "D6/AIN0_9") (pintype "unspecified"))
    )
    (net (code "18") (name "A-D7") (class "Default")
      (node (ref "J1") (pin "10") (pinfunction "D7/AIN1_10") (pintype "unspecified"))
      (node (ref "LED1") (pin "1") (pinfunction "1_1") (pintype "unspecified"))
      (node (ref "R5") (pin "2") (pinfunction "2_2") (pintype "unspecified"))
      (node (ref "U6") (pin "1") (pinfunction "1OUT_1") (pintype "unspecified"))
    )
    (net (code "19") (name "A-D8") (class "Default")
      (node (ref "J1") (pin "11") (pinfunction "D8/ICP_11") (pintype "unspecified"))
    )
    (net (code "20") (name "A-D9") (class "Default")
      (node (ref "H38") (pin "3") (pinfunction "3_3") (pintype "input"))
      (node (ref "J1") (pin "12") (pinfunction "D9/0C1_12") (pintype "unspecified"))
    )
    (net (code "21") (name "A-D10") (class "Default")
      (node (ref "J1") (pin "13") (pinfunction "D10_13") (pintype "unspecified"))
      (node (ref "P6") (pin "2") (pinfunction "2_2") (pintype "input"))
    )
    (net (code "22") (name "A-D11") (class "Default")
      (node (ref "J1") (pin "14") (pinfunction "D11/MOSI_14") (pintype "unspecified"))
    )
    (net (code "23") (name "A-D13") (class "Default")
      (node (ref "J1") (pin "16") (pinfunction "SCK/D13_16") (pintype "unspecified"))
    )
    (net (code "24") (name "A-Reset") (class "Default")
      (node (ref "J1") (pin "28") (pinfunction "RESET_28") (pintype "unspecified"))
      (node (ref "J1") (pin "3") (pinfunction "RESET_3") (pintype "unspecified"))
    )
    (net (code "25") (name "AC-L") (class "Default")
      (node (ref "H35") (pin "5") (pinfunction "5_5") (pintype "input"))
      (node (ref "H36") (pin "5") (pinfunction "5_5") (pintype "input"))
      (node (ref "H37") (pin "5") (pinfunction "5_5") (pintype "input"))
      (node (ref "H38") (pin "5") (pinfunction "5_5") (pintype "input"))
      (node (ref "P1") (pin "1") (pinfunction "1_1") (pintype "unspecified"))
    )
    (net (code "26") (name "AC-N") (class "Default")
      (node (ref "P1") (pin "3") (pinfunction "3_3") (pintype "unspecified"))
      (node (ref "P23") (pin "2") (pinfunction "2_2") (pintype "input"))
      (node (ref "P24") (pin "2") (pinfunction "2_2") (pintype "input"))
      (node (ref "P25") (pin "2") (pinfunction "2_2") (pintype "input"))
      (node (ref "P26") (pin "2") (pinfunction "2_2") (pintype "input"))
    )
    (net (code "27") (name "GND") (class "Default")
      (node (ref "C1") (pin "2") (pinfunction "2_2") (pintype "unspecified"))
      (node (ref "C2") (pin "2") (pinfunction "2_2") (pintype "unspecified"))
      (node (ref "C3") (pin "2") (pinfunction "2_2") (pintype "unspecified"))
      (node (ref "C4") (pin "2") (pinfunction "2_2") (pintype "unspecified"))
      (node (ref "CN1") (pin "1") (pinfunction "1_1") (pintype "unspecified"))
      (node (ref "CN2") (pin "1") (pinfunction "1_1") (pintype "unspecified"))
      (node (ref "CN3") (pin "1") (pinfunction "1_1") (pintype "unspecified"))
      (node (ref "CN4") (pin "1") (pinfunction "1_1") (pintype "unspecified"))
      (node (ref "DC1") (pin "2") (pinfunction "2_2") (pintype "unspecified"))
      (node (ref "H1") (pin "1") (pinfunction "1_1") (pintype "input"))
      (node (ref "H10") (pin "1") (pinfunction "1_1") (pintype "input"))
      (node (ref "H11") (pin "1") (pinfunction "1_1") (pintype "input"))
      (node (ref "H14") (pin "1") (pinfunction "1_1") (pintype "input"))
      (node (ref "H15") (pin "1") (pinfunction "1_1") (pintype "input"))
      (node (ref "H18") (pin "1") (pinfunction "1_1") (pintype "input"))
      (node (ref "H2") (pin "1") (pinfunction "1_1") (pintype "input"))
      (node (ref "H20") (pin "1") (pinfunction "1_1") (pintype "input"))
      (node (ref "H21") (pin "1") (pinfunction "1_1") (pintype "input"))
      (node (ref "H24") (pin "1") (pinfunction "1_1") (pintype "input"))
      (node (ref "H25") (pin "1") (pinfunction "1_1") (pintype "input"))
      (node (ref "H27") (pin "1") (pinfunction "1_1") (pintype "input"))
      (node (ref "H3") (pin "1") (pinfunction "1_1") (pintype "input"))
      (node (ref "H30") (pin "1") (pinfunction "1_1") (pintype "input"))
      (node (ref "H31") (pin "1") (pinfunction "1_1") (pintype "input"))
      (node (ref "H34") (pin "1") (pinfunction "1_1") (pintype "input"))
      (node (ref "H35") (pin "1") (pinfunction "1_1") (pintype "input"))
      (node (ref "H36") (pin "1") (pinfunction "1_1") (pintype "input"))
      (node (ref "H37") (pin "1") (pinfunction "1_1") (pintype "input"))
      (node (ref "H38") (pin "1") (pinfunction "1_1") (pintype "input"))
      (node (ref "H6") (pin "1") (pinfunction "1_1") (pintype "input"))
      (node (ref "H7") (pin "1") (pinfunction "1_1") (pintype "input"))
      (node (ref "J1") (pin "29") (pinfunction "GND_29") (pintype "unspecified"))
      (node (ref "J1") (pin "4") (pinfunction "GND_4") (pintype "unspecified"))
      (node (ref "P1") (pin "2") (pinfunction "2_2") (pintype "unspecified"))
      (node (ref "P3") (pin "1") (pinfunction "1_1") (pintype "input"))
      (node (ref "P4") (pin "1") (pinfunction "1_1") (pintype "input"))
      (node (ref "P5") (pin "3") (pinfunction "3_3") (pintype "input"))
      (node (ref "P6") (pin "3") (pinfunction "3_3") (pintype "input"))
      (node (ref "R3") (pin "2") (pinfunction "2_2") (pintype "unspecified"))
      (node (ref "R4") (pin "2") (pinfunction "2_2") (pintype "unspecified"))
      (node (ref "RP1") (pin "1") (pinfunction "1_1") (pintype "unspecified"))
      (node (ref "U2") (pin "12") (pinfunction "GND_12") (pintype "unspecified"))
      (node (ref "U2") (pin "16") (pinfunction "GND_16") (pintype "unspecified"))
      (node (ref "U2") (pin "7") (pinfunction "GND_7") (pintype "unspecified"))
      (node (ref "U3") (pin "1") (pinfunction "VSS_1") (pintype "unspecified"))
      (node (ref "U3") (pin "16") (pinfunction "A0_16") (pintype "unspecified"))
      (node (ref "U3") (pin "17") (pinfunction "A1_17") (pintype "unspecified"))
      (node (ref "U3") (pin "18") (pinfunction "A2_18") (pintype "unspecified"))
      (node (ref "U3") (pin "19") (pinfunction "VSS_19") (pintype "unspecified"))
      (node (ref "U3") (pin "8") (pinfunction "VSS_8") (pintype "unspecified"))
      (node (ref "U4") (pin "4") (pinfunction "G_4") (pintype "unspecified"))
      (node (ref "U5") (pin "2") (pinfunction "GND_2") (pintype "unspecified"))
      (node (ref "U6") (pin "4") (pinfunction "GND_4") (pintype "unspecified"))
    )
    (net (code "28") (name "GP0.0") (class "Default")
      (node (ref "H3") (pin "3") (pinfunction "3_3") (pintype "input"))
      (node (ref "U3") (pin "21") (pinfunction "GP0.0_21") (pintype "unspecified"))
    )
    (net (code "29") (name "GP0.1") (class "Default")
      (node (ref "H6") (pin "3") (pinfunction "3_3") (pintype "input"))
      (node (ref "U3") (pin "22") (pinfunction "GP0.1_22") (pintype "unspecified"))
    )
    (net (code "30") (name "GP0.2") (class "Default")
      (node (ref "H7") (pin "3") (pinfunction "3_3") (pintype "input"))
      (node (ref "U3") (pin "23") (pinfunction "GP0.2_23") (pintype "unspecified"))
    )
    (net (code "31") (name "GP0.3") (class "Default")
      (node (ref "H10") (pin "3") (pinfunction "3_3") (pintype "input"))
      (node (ref "U3") (pin "24") (pinfunction "GP0.3_24") (pintype "unspecified"))
    )
    (net (code "32") (name "GP0.4") (class "Default")
      (node (ref "H18") (pin "3") (pinfunction "3_3") (pintype "input"))
      (node (ref "U3") (pin "25") (pinfunction "GP0.4_25") (pintype "unspecified"))
    )
    (net (code "33") (name "GP0.5") (class "Default")
      (node (ref "H15") (pin "3") (pinfunction "3_3") (pintype "input"))
      (node (ref "U3") (pin "26") (pinfunction "GP0.5_26") (pintype "unspecified"))
    )
    (net (code "34") (name "GP0.6") (class "Default")
      (node (ref "H14") (pin "3") (pinfunction "3_3") (pintype "input"))
      (node (ref "U3") (pin "27") (pinfunction "GP0.6_27") (pintype "unspecified"))
    )
    (net (code "35") (name "GP0.7") (class "Default")
      (node (ref "H11") (pin "3") (pinfunction "3_3") (pintype "input"))
      (node (ref "U3") (pin "28") (pinfunction "GP0.7_28") (pintype "unspecified"))
    )
    (net (code "36") (name "GP1.0") (class "Default")
      (node (ref "H20") (pin "3") (pinfunction "3_3") (pintype "input"))
      (node (ref "U3") (pin "2") (pinfunction "GP1.0_2") (pintype "unspecified"))
    )
    (net (code "37") (name "GP1.1") (class "Default")
      (node (ref "H21") (pin "3") (pinfunction "3_3") (pintype "input"))
      (node (ref "U3") (pin "3") (pinfunction "GP1.1_3") (pintype "unspecified"))
    )
    (net (code "38") (name "GP1.2") (class "Default")
      (node (ref "H25") (pin "3") (pinfunction "3_3") (pintype "input"))
      (node (ref "U3") (pin "4") (pinfunction "GP1.2_4") (pintype "unspecified"))
    )
    (net (code "39") (name "GP1.3") (class "Default")
      (node (ref "H24") (pin "3") (pinfunction "3_3") (pintype "input"))
      (node (ref "U3") (pin "5") (pinfunction "GP1.3_5") (pintype "unspecified"))
    )
    (net (code "40") (name "GP1.4") (class "Default")
      (node (ref "H27") (pin "3") (pinfunction "3_3") (pintype "input"))
      (node (ref "U3") (pin "7") (pinfunction "GP1.4_7") (pintype "unspecified"))
    )
    (net (code "41") (name "GP1.5") (class "Default")
      (node (ref "H34") (pin "3") (pinfunction "3_3") (pintype "input"))
      (node (ref "U3") (pin "11") (pinfunction "GP1.5_11") (pintype "unspecified"))
    )
    (net (code "42") (name "GP1.6") (class "Default")
      (node (ref "H31") (pin "3") (pinfunction "3_3") (pintype "input"))
      (node (ref "U3") (pin "12") (pinfunction "GP1.6_12") (pintype "unspecified"))
    )
    (net (code "43") (name "GP1.7") (class "Default")
      (node (ref "H30") (pin "3") (pinfunction "3_3") (pintype "input"))
      (node (ref "U3") (pin "13") (pinfunction "GP1.7_13") (pintype "unspecified"))
    )
    (net (code "44") (name "GPCLK") (class "Default")
      (node (ref "C4") (pin "1") (pinfunction "1_1") (pintype "unspecified"))
      (node (ref "R6") (pin "2") (pinfunction "2_2") (pintype "unspecified"))
      (node (ref "U3") (pin "9") (pinfunction "CLK_9") (pintype "unspecified"))
    )
    (net (code "45") (name "Net-(C3-Pad1)") (class "Default")
      (node (ref "C3") (pin "1") (pinfunction "1_1") (pintype "unspecified"))
      (node (ref "LED1") (pin "2") (pinfunction "2_2") (pintype "unspecified"))
    )
    (net (code "46") (name "Net-(CN1-Pad3)") (class "Default")
      (node (ref "CN1") (pin "3") (pinfunction "3_3") (pintype "unspecified"))
      (node (ref "CN2") (pin "3") (pinfunction "3_3") (pintype "unspecified"))
      (node (ref "CN3") (pin "3") (pinfunction "3_3") (pintype "unspecified"))
      (node (ref "CN4") (pin "3") (pinfunction "3_3") (pintype "unspecified"))
    )
    (net (code "47") (name "Net-(CN1-Pad4)") (class "Default")
      (node (ref "CN1") (pin "4") (pinfunction "4_4") (pintype "unspecified"))
      (node (ref "CN2") (pin "4") (pinfunction "4_4") (pintype "unspecified"))
      (node (ref "CN3") (pin "4") (pinfunction "4_4") (pintype "unspecified"))
      (node (ref "CN4") (pin "4") (pinfunction "4_4") (pintype "unspecified"))
    )
    (net (code "48") (name "Net-(DC1-Pad1)") (class "Default")
      (node (ref "DC1") (pin "1") (pinfunction "1_1") (pintype "unspecified"))
      (node (ref "SW1") (pin "1") (pinfunction "1_1") (pintype "unspecified"))
    )
    (net (code "49") (name "Net-(H1-Pad4)") (class "Default")
      (node (ref "H1") (pin "4") (pinfunction "4_4") (pintype "input"))
      (node (ref "H1") (pin "6") (pinfunction "6_6") (pintype "input"))
      (node (ref "RF1") (pin "3") (pinfunction "3_3") (pintype "unspecified"))
    )
    (net (code "50") (name "Net-(H1-Pad5)") (class "Default")
      (node (ref "H1") (pin "5") (pinfunction "5_5") (pintype "input"))
      (node (ref "RF1") (pin "1") (pinfunction "1_1") (pintype "unspecified"))
    )
    (net (code "51") (name "Net-(H2-Pad4)") (class "Default")
      (node (ref "H2") (pin "4") (pinfunction "4_4") (pintype "input"))
      (node (ref "H2") (pin "6") (pinfunction "6_6") (pintype "input"))
      (node (ref "RF1") (pin "4") (pinfunction "4_4") (pintype "unspecified"))
    )
    (net (code "52") (name "Net-(H2-Pad5)") (class "Default")
      (node (ref "H2") (pin "5") (pinfunction "5_5") (pintype "input"))
      (node (ref "RF1") (pin "2") (pinfunction "2_2") (pintype "unspecified"))
    )
    (net (code "53") (name "Net-(H3-Pad4)") (class "Default")
      (node (ref "H3") (pin "4") (pinfunction "4_4") (pintype "input"))
      (node (ref "P13") (pin "1") (pinfunction "1_1") (pintype "unspecified"))
    )
    (net (code "54") (name "Net-(H3-Pad5)") (class "Default")
      (node (ref "H3") (pin "5") (pinfunction "5_5") (pintype "input"))
      (node (ref "H4") (pin "1") (pinfunction "1_1") (pintype "unspecified"))
      (node (ref "P13") (pin "3") (pinfunction "3_3") (pintype "unspecified"))
    )
    (net (code "55") (name "Net-(H3-Pad6)") (class "Default")
      (node (ref "H3") (pin "6") (pinfunction "6_6") (pintype "input"))
      (node (ref "P13") (pin "2") (pinfunction "2_2") (pintype "unspecified"))
    )
    (net (code "56") (name "Net-(H5-Pad1)") (class "Default")
      (node (ref "H5") (pin "1") (pinfunction "1_1") (pintype "unspecified"))
      (node (ref "H6") (pin "5") (pinfunction "5_5") (pintype "input"))
      (node (ref "P12") (pin "3") (pinfunction "3_3") (pintype "unspecified"))
    )
    (net (code "57") (name "Net-(H6-Pad4)") (class "Default")
      (node (ref "H6") (pin "4") (pinfunction "4_4") (pintype "input"))
      (node (ref "P12") (pin "1") (pinfunction "1_1") (pintype "unspecified"))
    )
    (net (code "58") (name "Net-(H6-Pad6)") (class "Default")
      (node (ref "H6") (pin "6") (pinfunction "6_6") (pintype "input"))
      (node (ref "P12") (pin "2") (pinfunction "2_2") (pintype "unspecified"))
    )
    (net (code "59") (name "Net-(H7-Pad4)") (class "Default")
      (node (ref "H7") (pin "4") (pinfunction "4_4") (pintype "input"))
      (node (ref "P11") (pin "1") (pinfunction "1_1") (pintype "unspecified"))
    )
    (net (code "60") (name "Net-(H7-Pad5)") (class "Default")
      (node (ref "H7") (pin "5") (pinfunction "5_5") (pintype "input"))
      (node (ref "H8") (pin "1") (pinfunction "1_1") (pintype "unspecified"))
      (node (ref "P11") (pin "3") (pinfunction "3_3") (pintype "unspecified"))
    )
    (net (code "61") (name "Net-(H7-Pad6)") (class "Default")
      (node (ref "H7") (pin "6") (pinfunction "6_6") (pintype "input"))
      (node (ref "P11") (pin "2") (pinfunction "2_2") (pintype "unspecified"))
    )
    (net (code "62") (name "Net-(H10-Pad4)") (class "Default")
      (node (ref "H10") (pin "4") (pinfunction "4_4") (pintype "input"))
      (node (ref "P16") (pin "1") (pinfunction "1_1") (pintype "unspecified"))
    )
    (net (code "63") (name "Net-(H10-Pad5)") (class "Default")
      (node (ref "H10") (pin "5") (pinfunction "5_5") (pintype "input"))
      (node (ref "H9") (pin "1") (pinfunction "1_1") (pintype "unspecified"))
      (node (ref "P16") (pin "3") (pinfunction "3_3") (pintype "unspecified"))
    )
    (net (code "64") (name "Net-(H10-Pad6)") (class "Default")
      (node (ref "H10") (pin "6") (pinfunction "6_6") (pintype "input"))
      (node (ref "P16") (pin "2") (pinfunction "2_2") (pintype "unspecified"))
    )
    (net (code "65") (name "Net-(H11-Pad4)") (class "Default")
      (node (ref "H11") (pin "4") (pinfunction "4_4") (pintype "input"))
      (node (ref "P17") (pin "1") (pinfunction "1_1") (pintype "unspecified"))
    )
    (net (code "66") (name "Net-(H11-Pad5)") (class "Default")
      (node (ref "H11") (pin "5") (pinfunction "5_5") (pintype "input"))
      (node (ref "H12") (pin "1") (pinfunction "1_1") (pintype "unspecified"))
      (node (ref "P17") (pin "3") (pinfunction "3_3") (pintype "unspecified"))
    )
    (net (code "67") (name "Net-(H11-Pad6)") (class "Default")
      (node (ref "H11") (pin "6") (pinfunction "6_6") (pintype "input"))
      (node (ref "P17") (pin "2") (pinfunction "2_2") (pintype "unspecified"))
    )
    (net (code "68") (name "Net-(H13-Pad1)") (class "Default")
      (node (ref "H13") (pin "1") (pinfunction "1_1") (pintype "unspecified"))
      (node (ref "H14") (pin "5") (pinfunction "5_5") (pintype "input"))
      (node (ref "P8") (pin "3") (pinfunction "3_3") (pintype "unspecified"))
    )
    (net (code "69") (name "Net-(H14-Pad4)") (class "Default")
      (node (ref "H14") (pin "4") (pinfunction "4_4") (pintype "input"))
      (node (ref "P8") (pin "1") (pinfunction "1_1") (pintype "unspecified"))
    )
    (net (code "70") (name "Net-(H14-Pad6)") (class "Default")
      (node (ref "H14") (pin "6") (pinfunction "6_6") (pintype "input"))
      (node (ref "P8") (pin "2") (pinfunction "2_2") (pintype "unspecified"))
    )
    (net (code "71") (name "Net-(H15-Pad4)") (class "Default")
      (node (ref "H15") (pin "4") (pinfunction "4_4") (pintype "input"))
      (node (ref "P10") (pin "1") (pinfunction "1_1") (pintype "unspecified"))
    )
    (net (code "72") (name "Net-(H15-Pad5)") (class "Default")
      (node (ref "H15") (pin "5") (pinfunction "5_5") (pintype "input"))
      (node (ref "H16") (pin "1") (pinfunction "1_1") (pintype "unspecified"))
      (node (ref "P10") (pin "3") (pinfunction "3_3") (pintype "unspecified"))
    )
    (net (code "73") (name "Net-(H15-Pad6)") (class "Default")
      (node (ref "H15") (pin "6") (pinfunction "6_6") (pintype "input"))
      (node (ref "P10") (pin "2") (pinfunction "2_2") (pintype "unspecified"))
    )
    (net (code "74") (name "Net-(H17-Pad1)") (class "Default")
      (node (ref "H17") (pin "1") (pinfunction "1_1") (pintype "unspecified"))
      (node (ref "H18") (pin "5") (pinfunction "5_5") (pintype "input"))
      (node (ref "P14") (pin "3") (pinfunction "3_3") (pintype "unspecified"))
    )
    (net (code "75") (name "Net-(H18-Pad4)") (class "Default")
      (node (ref "H18") (pin "4") (pinfunction "4_4") (pintype "input"))
      (node (ref "P14") (pin "1") (pinfunction "1_1") (pintype "unspecified"))
    )
    (net (code "76") (name "Net-(H18-Pad6)") (class "Default")
      (node (ref "H18") (pin "6") (pinfunction "6_6") (pintype "input"))
      (node (ref "P14") (pin "2") (pinfunction "2_2") (pintype "unspecified"))
    )
    (net (code "77") (name "Net-(H19-Pad1)") (class "Default")
      (node (ref "H19") (pin "1") (pinfunction "1_1") (pintype "unspecified"))
      (node (ref "H20") (pin "5") (pinfunction "5_5") (pintype "input"))
      (node (ref "P18") (pin "3") (pinfunction "3_3") (pintype "unspecified"))
    )
    (net (code "78") (name "Net-(H20-Pad4)") (class "Default")
      (node (ref "H20") (pin "4") (pinfunction "4_4") (pintype "input"))
      (node (ref "P18") (pin "1") (pinfunction "1_1") (pintype "unspecified"))
    )
    (net (code "79") (name "Net-(H20-Pad6)") (class "Default")
      (node (ref "H20") (pin "6") (pinfunction "6_6") (pintype "input"))
      (node (ref "P18") (pin "2") (pinfunction "2_2") (pintype "unspecified"))
    )
    (net (code "80") (name "Net-(H21-Pad4)") (class "Default")
      (node (ref "H21") (pin "4") (pinfunction "4_4") (pintype "input"))
      (node (ref "P19") (pin "1") (pinfunction "1_1") (pintype "unspecified"))
    )
    (net (code "81") (name "Net-(H21-Pad5)") (class "Default")
      (node (ref "H21") (pin "5") (pinfunction "5_5") (pintype "input"))
      (node (ref "H22") (pin "1") (pinfunction "1_1") (pintype "unspecified"))
      (node (ref "P19") (pin "3") (pinfunction "3_3") (pintype "unspecified"))
    )
    (net (code "82") (name "Net-(H21-Pad6)") (class "Default")
      (node (ref "H21") (pin "6") (pinfunction "6_6") (pintype "input"))
      (node (ref "P19") (pin "2") (pinfunction "2_2") (pintype "unspecified"))
    )
    (net (code "83") (name "Net-(H23-Pad1)") (class "Default")
      (node (ref "H23") (pin "1") (pinfunction "1_1") (pintype "unspecified"))
      (node (ref "H24") (pin "5") (pinfunction "5_5") (pintype "input"))
      (node (ref "P20") (pin "3") (pinfunction "3_3") (pintype "unspecified"))
    )
    (net (code "84") (name "Net-(H24-Pad4)") (class "Default")
      (node (ref "H24") (pin "4") (pinfunction "4_4") (pintype "input"))
      (node (ref "P20") (pin "1") (pinfunction "1_1") (pintype "unspecified"))
    )
    (net (code "85") (name "Net-(H24-Pad6)") (class "Default")
      (node (ref "H24") (pin "6") (pinfunction "6_6") (pintype "input"))
      (node (ref "P20") (pin "2") (pinfunction "2_2") (pintype "unspecified"))
    )
    (net (code "86") (name "Net-(H25-Pad4)") (class "Default")
      (node (ref "H25") (pin "4") (pinfunction "4_4") (pintype "input"))
      (node (ref "P21") (pin "1") (pinfunction "1_1") (pintype "unspecified"))
    )
    (net (code "87") (name "Net-(H25-Pad5)") (class "Default")
      (node (ref "H25") (pin "5") (pinfunction "5_5") (pintype "input"))
      (node (ref "H26") (pin "1") (pinfunction "1_1") (pintype "unspecified"))
      (node (ref "P21") (pin "3") (pinfunction "3_3") (pintype "unspecified"))
    )
    (net (code "88") (name "Net-(H25-Pad6)") (class "Default")
      (node (ref "H25") (pin "6") (pinfunction "6_6") (pintype "input"))
      (node (ref "P21") (pin "2") (pinfunction "2_2") (pintype "unspecified"))
    )
    (net (code "89") (name "Net-(H27-Pad4)") (class "Default")
      (node (ref "H27") (pin "4") (pinfunction "4_4") (pintype "input"))
      (node (ref "P22") (pin "1") (pinfunction "1_1") (pintype "unspecified"))
    )
    (net (code "90") (name "Net-(H27-Pad5)") (class "Default")
      (node (ref "H27") (pin "5") (pinfunction "5_5") (pintype "input"))
      (node (ref "H28") (pin "1") (pinfunction "1_1") (pintype "unspecified"))
      (node (ref "P22") (pin "3") (pinfunction "3_3") (pintype "unspecified"))
    )
    (net (code "91") (name "Net-(H27-Pad6)") (class "Default")
      (node (ref "H27") (pin "6") (pinfunction "6_6") (pintype "input"))
      (node (ref "P22") (pin "2") (pinfunction "2_2") (pintype "unspecified"))
    )
    (net (code "92") (name "Net-(H29-Pad1)") (class "Default")
      (node (ref "H29") (pin "1") (pinfunction "1_1") (pintype "unspecified"))
      (node (ref "H30") (pin "5") (pinfunction "5_5") (pintype "input"))
      (node (ref "P7") (pin "3") (pinfunction "3_3") (pintype "unspecified"))
    )
    (net (code "93") (name "Net-(H30-Pad4)") (class "Default")
      (node (ref "H30") (pin "4") (pinfunction "4_4") (pintype "input"))
      (node (ref "P7") (pin "1") (pinfunction "1_1") (pintype "unspecified"))
    )
    (net (code "94") (name "Net-(H30-Pad6)") (class "Default")
      (node (ref "H30") (pin "6") (pinfunction "6_6") (pintype "input"))
      (node (ref "P7") (pin "2") (pinfunction "2_2") (pintype "unspecified"))
    )
    (net (code "95") (name "Net-(H31-Pad4)") (class "Default")
      (node (ref "H31") (pin "4") (pinfunction "4_4") (pintype "input"))
      (node (ref "P9") (pin "1") (pinfunction "1_1") (pintype "unspecified"))
    )
    (net (code "96") (name "Net-(H31-Pad5)") (class "Default")
      (node (ref "H31") (pin "5") (pinfunction "5_5") (pintype "input"))
      (node (ref "H32") (pin "1") (pinfunction "1_1") (pintype "unspecified"))
      (node (ref "P9") (pin "3") (pinfunction "3_3") (pintype "unspecified"))
    )
    (net (code "97") (name "Net-(H31-Pad6)") (class "Default")
      (node (ref "H31") (pin "6") (pinfunction "6_6") (pintype "input"))
      (node (ref "P9") (pin "2") (pinfunction "2_2") (pintype "unspecified"))
    )
    (net (code "98") (name "Net-(H33-Pad1)") (class "Default")
      (node (ref "H33") (pin "1") (pinfunction "1_1") (pintype "unspecified"))
      (node (ref "H34") (pin "5") (pinfunction "5_5") (pintype "input"))
      (node (ref "P15") (pin "3") (pinfunction "3_3") (pintype "unspecified"))
    )
    (net (code "99") (name "Net-(H34-Pad4)") (class "Default")
      (node (ref "H34") (pin "4") (pinfunction "4_4") (pintype "input"))
      (node (ref "P15") (pin "1") (pinfunction "1_1") (pintype "unspecified"))
    )
    (net (code "100") (name "Net-(H34-Pad6)") (class "Default")
      (node (ref "H34") (pin "6") (pinfunction "6_6") (pintype "input"))
      (node (ref "P15") (pin "2") (pinfunction "2_2") (pintype "unspecified"))
    )
    (net (code "101") (name "Net-(H35-Pad4)") (class "Default")
      (node (ref "H35") (pin "4") (pinfunction "4_4") (pintype "input"))
      (node (ref "P24") (pin "1") (pinfunction "1_1") (pintype "input"))
    )
    (net (code "102") (name "Net-(H36-Pad4)") (class "Default")
      (node (ref "H36") (pin "4") (pinfunction "4_4") (pintype "input"))
      (node (ref "P23") (pin "1") (pinfunction "1_1") (pintype "input"))
    )
    (net (code "103") (name "Net-(H37-Pad4)") (class "Default")
      (node (ref "H37") (pin "4") (pinfunction "4_4") (pintype "input"))
      (node (ref "P25") (pin "1") (pinfunction "1_1") (pintype "input"))
    )
    (net (code "104") (name "Net-(H38-Pad4)") (class "Default")
      (node (ref "H38") (pin "4") (pinfunction "4_4") (pintype "input"))
      (node (ref "P26") (pin "1") (pinfunction "1_1") (pintype "input"))
    )
    (net (code "105") (name "Net-(R3-Pad1)") (class "Default")
      (node (ref "R3") (pin "1") (pinfunction "1_1") (pintype "unspecified"))
      (node (ref "U7") (pin "5") (pinfunction "5_5") (pintype "unspecified"))
    )
    (net (code "106") (name "Net-(U6-1IN+)") (class "Default")
      (node (ref "RP1") (pin "2") (pinfunction "2_2") (pintype "unspecified"))
      (node (ref "U6") (pin "3") (pinfunction "1IN+_3") (pintype "unspecified"))
    )
    (net (code "107") (name "unconnected-(DC1-Pad3)") (class "Default")
      (node (ref "DC1") (pin "3") (pinfunction "3_3") (pintype "unspecified"))
    )
    (net (code "108") (name "unconnected-(H35-Pad6)") (class "Default")
      (node (ref "H35") (pin "6") (pinfunction "6_6") (pintype "input"))
    )
    (net (code "109") (name "unconnected-(H36-Pad6)") (class "Default")
      (node (ref "H36") (pin "6") (pinfunction "6_6") (pintype "input"))
    )
    (net (code "110") (name "unconnected-(H37-Pad6)") (class "Default")
      (node (ref "H37") (pin "6") (pinfunction "6_6") (pintype "input"))
    )
    (net (code "111") (name "unconnected-(H38-Pad6)") (class "Default")
      (node (ref "H38") (pin "6") (pinfunction "6_6") (pintype "input"))
    )
    (net (code "112") (name "unconnected-(J1-3V3-Pad17)") (class "Default")
      (node (ref "J1") (pin "17") (pinfunction "3V3_17") (pintype "unspecified"))
    )
    (net (code "113") (name "unconnected-(J1-5V-Pad27)") (class "Default")
      (node (ref "J1") (pin "27") (pinfunction "5V_27") (pintype "unspecified"))
    )
    (net (code "114") (name "unconnected-(SW1-Pad3)") (class "Default")
      (node (ref "SW1") (pin "3") (pinfunction "3_3") (pintype "unspecified"))
    )
    (net (code "115") (name "unconnected-(SW1-Pad4)") (class "Default")
      (node (ref "SW1") (pin "4") (pinfunction "4_4") (pintype "unspecified"))
    )
    (net (code "116") (name "unconnected-(SW1-Pad5)") (class "Default")
      (node (ref "SW1") (pin "5") (pinfunction "5_5") (pintype "unspecified"))
    )
    (net (code "117") (name "unconnected-(U2-3V3-Pad9)") (class "Default")
      (node (ref "U2") (pin "9") (pinfunction "3V3_9") (pintype "unspecified"))
    )
    (net (code "118") (name "unconnected-(U2-5V-Pad8)") (class "Default")
      (node (ref "U2") (pin "8") (pinfunction "5V_8") (pintype "unspecified"))
    )
    (net (code "119") (name "unconnected-(U2-IO0-Pad11)") (class "Default")
      (node (ref "U2") (pin "11") (pinfunction "IO0_11") (pintype "unspecified"))
    )
    (net (code "120") (name "unconnected-(U2-IO2-Pad2)") (class "Default")
      (node (ref "U2") (pin "2") (pinfunction "IO2_2") (pintype "unspecified"))
    )
    (net (code "121") (name "unconnected-(U2-IO4-Pad1)") (class "Default")
      (node (ref "U2") (pin "1") (pinfunction "IO4_1") (pintype "unspecified"))
    )
    (net (code "122") (name "unconnected-(U2-IO12-Pad6)") (class "Default")
      (node (ref "U2") (pin "6") (pinfunction "IO12_6") (pintype "unspecified"))
    )
    (net (code "123") (name "unconnected-(U2-IO13-Pad5)") (class "Default")
      (node (ref "U2") (pin "5") (pinfunction "IO13_5") (pintype "unspecified"))
    )
    (net (code "124") (name "unconnected-(U2-IO14-Pad3)") (class "Default")
      (node (ref "U2") (pin "3") (pinfunction "IO14_3") (pintype "unspecified"))
    )
    (net (code "125") (name "unconnected-(U2-IO15-Pad4)") (class "Default")
      (node (ref "U2") (pin "4") (pinfunction "IO15_4") (pintype "unspecified"))
    )
    (net (code "126") (name "unconnected-(U2-IO16-Pad10)") (class "Default")
      (node (ref "U2") (pin "10") (pinfunction "IO16_10") (pintype "unspecified"))
    )
    (net (code "127") (name "unconnected-(U3-TP-Pad10)") (class "Default")
      (node (ref "U3") (pin "10") (pinfunction "TP_10") (pintype "unspecified"))
    )
    (net (code "128") (name "unconnected-(U3-nINT-Pad6)") (class "Default")
      (node (ref "U3") (pin "6") (pinfunction "nINT_6") (pintype "unspecified"))
    )
    (net (code "129") (name "unconnected-(U4-N-Pad3)") (class "Default")
      (node (ref "U4") (pin "3") (pinfunction "N_3") (pintype "unspecified"))
    )
    (net (code "130") (name "unconnected-(U6-2IN+-Pad5)") (class "Default")
      (node (ref "U6") (pin "5") (pinfunction "2IN+_5") (pintype "unspecified"))
    )
    (net (code "131") (name "unconnected-(U6-2IN−-Pad6)") (class "Default")
      (node (ref "U6") (pin "6") (pinfunction "2IN−_6") (pintype "unspecified"))
    )
    (net (code "132") (name "unconnected-(U6-2OUT-Pad7)") (class "Default")
      (node (ref "U6") (pin "7") (pinfunction "2OUT_7") (pintype "unspecified"))
    )
  )
)
